# mcu.net
KiCad netlist of a schematic drawn in Altium Designer
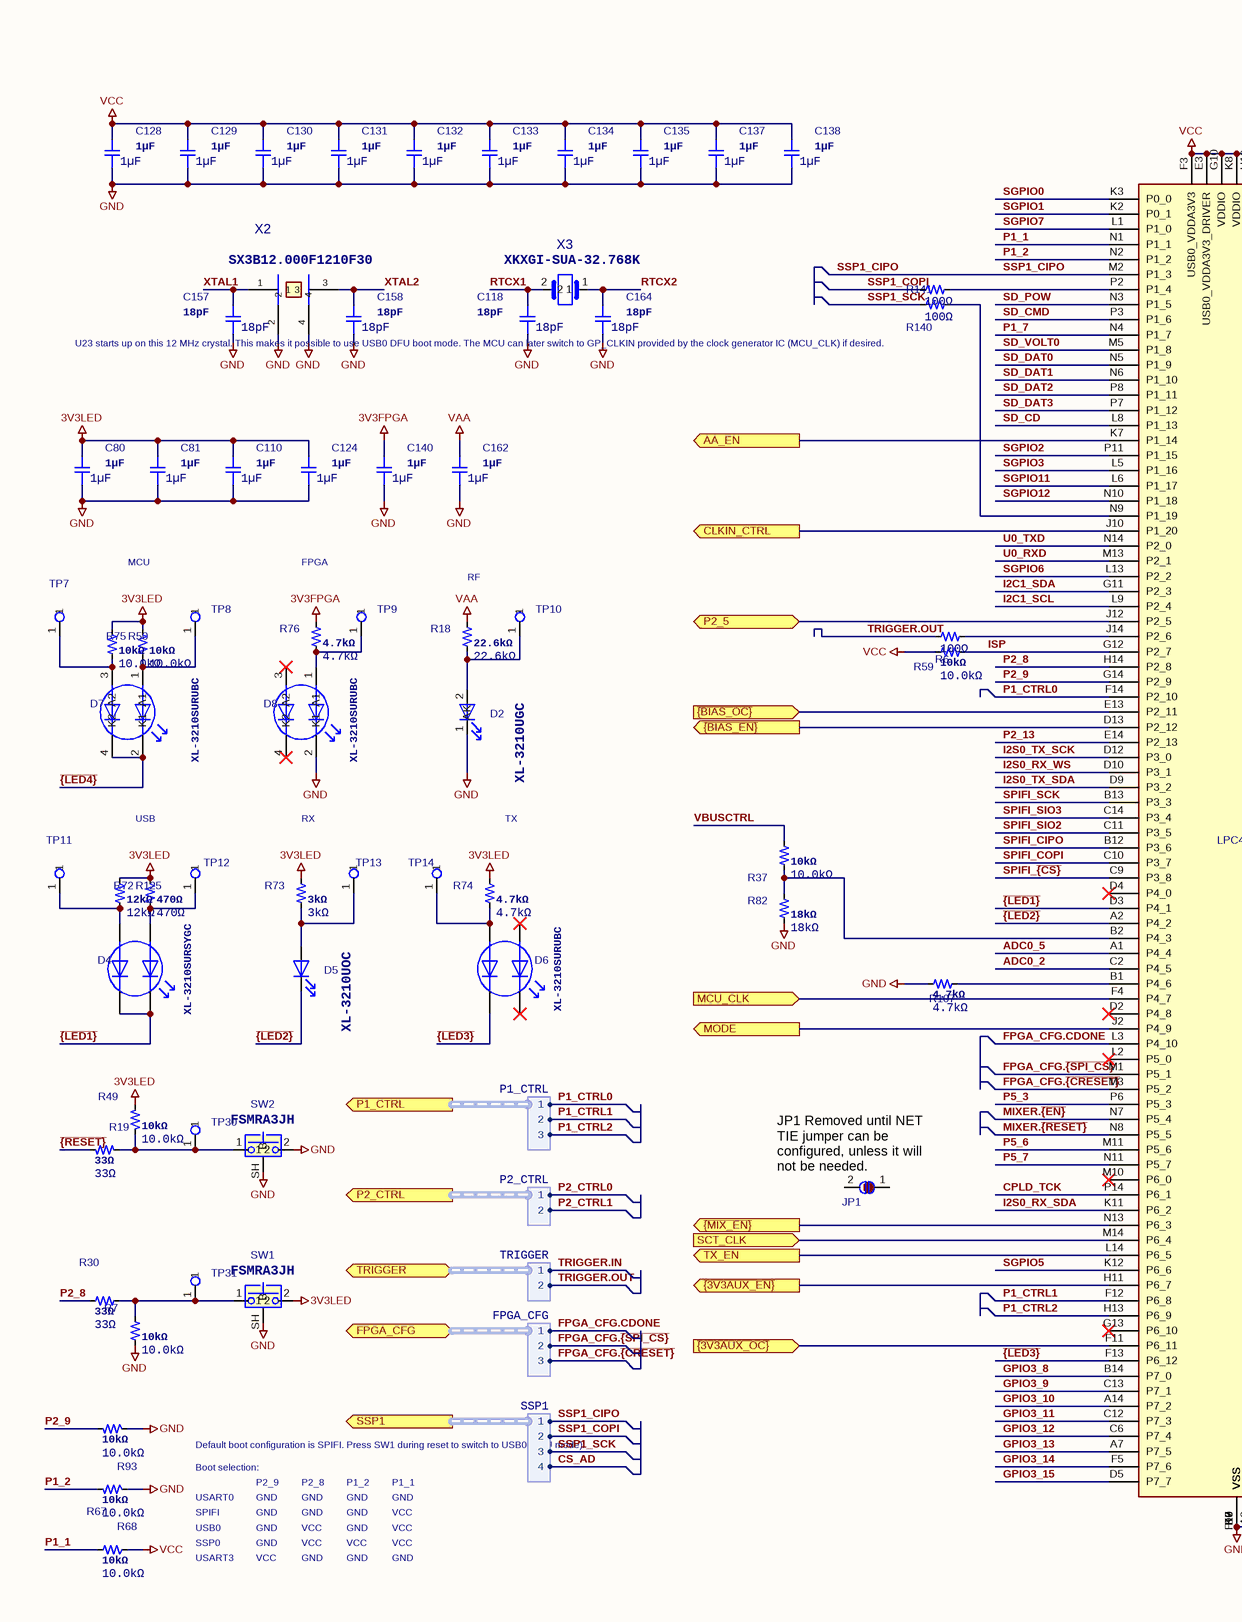
[diagram p0: mcu.SchDoc, left]
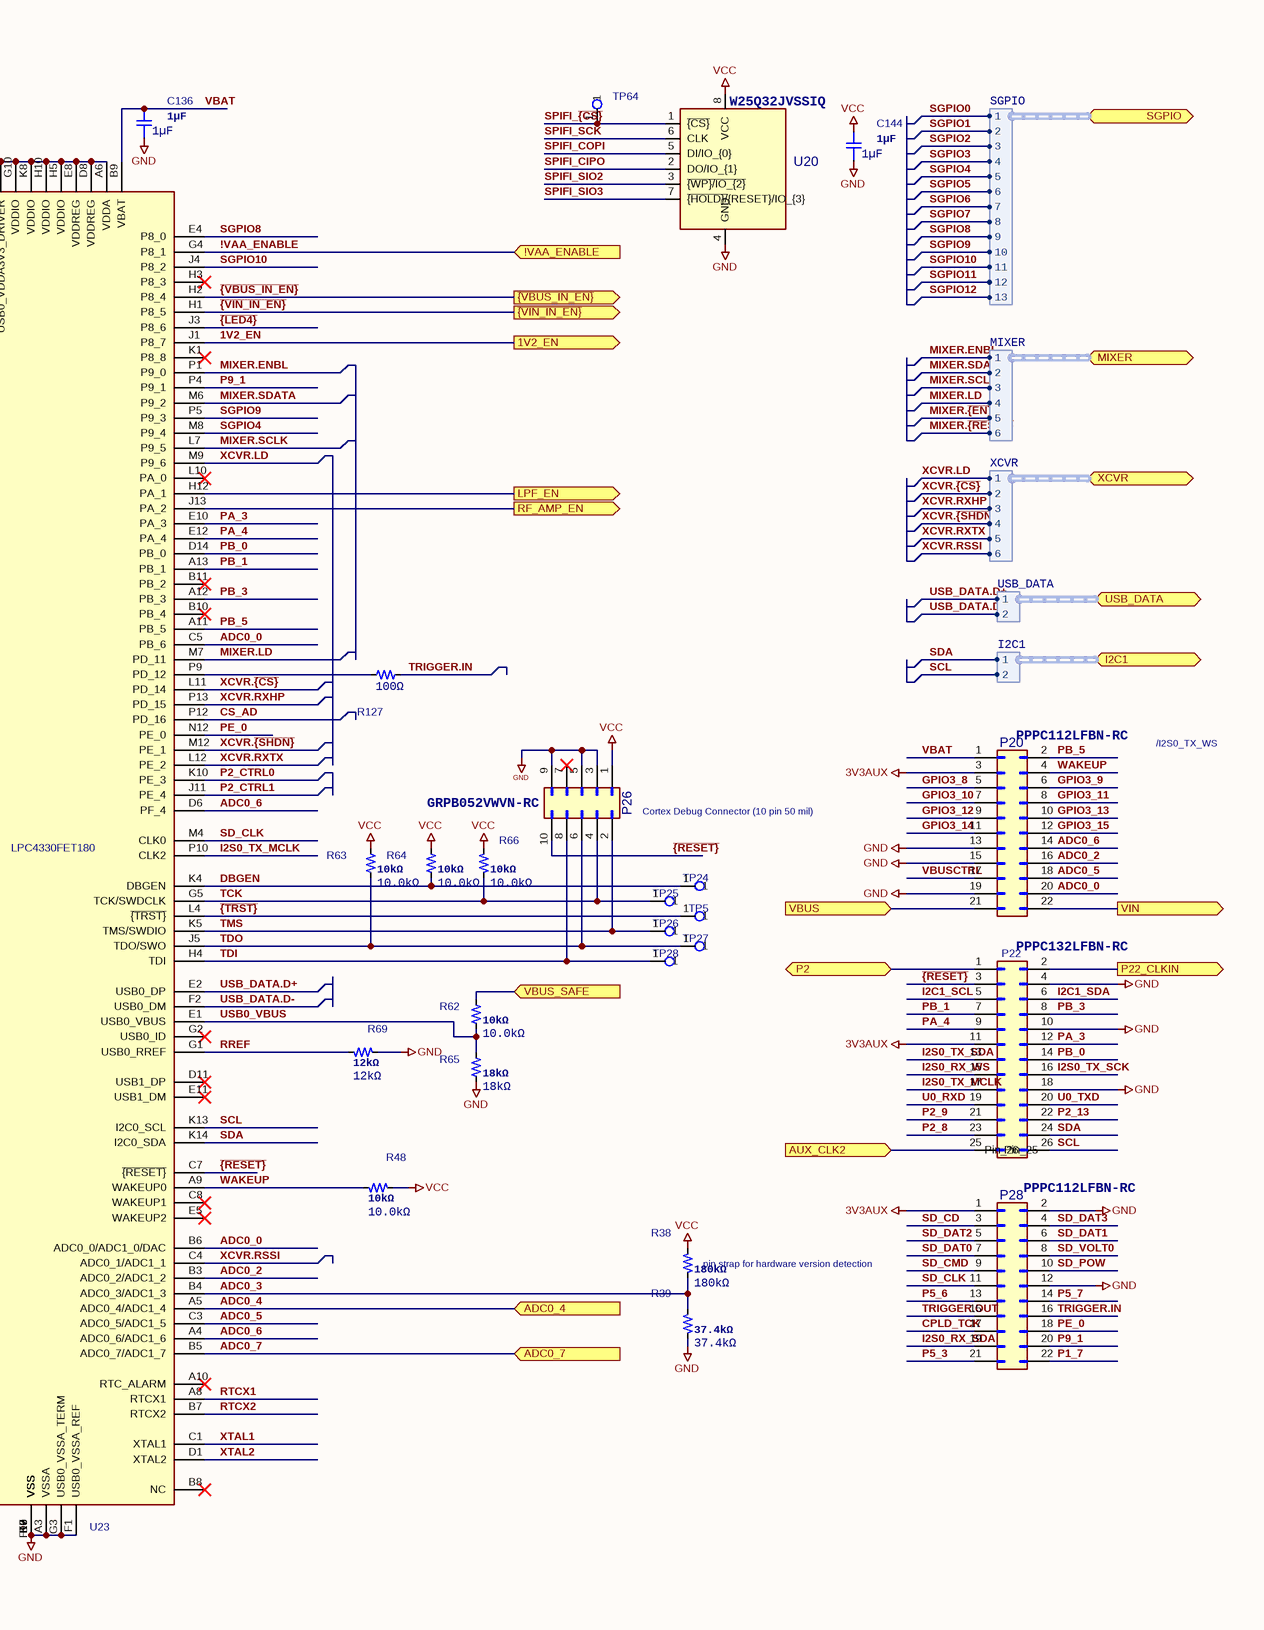
[diagram p1: mcu.SchDoc, right]

(export (version "E")
  (design (tool "Eeschema 10.0.6"))
  (components
    (comp (ref "C80")
      (value "1µF")
      (footprint "CAPC0402(1005)33_L")
      (description "CAP, CERM, 1 µF, 25 V, +/-10%, 0402, X7R")
      (fields
        (field (name "CAPACITANCE") "1µF")
        (field (name "VOLTAGE") "25V")
        (field (name "TOLERANCE") "10%")
      )
      (libsource (lib "Micro Nova LLC") (part "Standard Capacitor"))
    )
    (comp (ref "C81")
      (value "1µF")
      (footprint "CAPC0402(1005)33_L")
      (description "CAP, CERM, 1 µF, 25 V, +/-10%, 0402, X7R")
      (fields
        (field (name "CAPACITANCE") "1µF")
        (field (name "VOLTAGE") "25V")
        (field (name "TOLERANCE") "10%")
      )
      (libsource (lib "Micro Nova LLC") (part "Standard Capacitor"))
    )
    (comp (ref "C110")
      (value "1µF")
      (footprint "CAPC0402(1005)33_L")
      (description "CAP, CERM, 1 µF, 25 V, +/-10%, 0402, X7R")
      (fields
        (field (name "CAPACITANCE") "1µF")
        (field (name "VOLTAGE") "25V")
        (field (name "TOLERANCE") "10%")
      )
      (libsource (lib "Micro Nova LLC") (part "Standard Capacitor"))
    )
    (comp (ref "C118")
      (value "18pF")
      (footprint "CAPC0402(1005)33_L")
      (description "CAP, CERM, 18 pF, 50 V, +/-5%, 0402, C0G")
      (fields
        (field (name "CAPACITANCE") "18pF")
        (field (name "TOLERANCE") "5%")
        (field (name "PARTNUMBER") "CGA2B2NP01H220J050BA")
      )
      (libsource (lib "Micro Nova LLC") (part "Standard Capacitor"))
    )
    (comp (ref "C124")
      (value "1µF")
      (footprint "CAPC0402(1005)33_L")
      (description "CAP, CERM, 1 µF, 25 V, +/-10%, 0402, X7R")
      (fields
        (field (name "CAPACITANCE") "1µF")
        (field (name "VOLTAGE") "25V")
        (field (name "TOLERANCE") "10%")
      )
      (libsource (lib "Micro Nova LLC") (part "Standard Capacitor"))
    )
    (comp (ref "C128")
      (value "1µF")
      (footprint "CAPC0402(1005)33_L")
      (description "CAP, CERM, 1 µF, 25 V, +/-10%, 0402, X7R")
      (fields
        (field (name "CAPACITANCE") "1µF")
        (field (name "VOLTAGE") "25V")
        (field (name "TOLERANCE") "10%")
      )
      (libsource (lib "Micro Nova LLC") (part "Standard Capacitor"))
    )
    (comp (ref "C129")
      (value "1µF")
      (footprint "CAPC0402(1005)33_L")
      (description "CAP, CERM, 1 µF, 25 V, +/-10%, 0402, X7R")
      (fields
        (field (name "CAPACITANCE") "1µF")
        (field (name "VOLTAGE") "25V")
        (field (name "TOLERANCE") "10%")
      )
      (libsource (lib "Micro Nova LLC") (part "Standard Capacitor"))
    )
    (comp (ref "C130")
      (value "1µF")
      (footprint "CAPC0402(1005)33_L")
      (description "CAP, CERM, 1 µF, 25 V, +/-10%, 0402, X7R")
      (fields
        (field (name "CAPACITANCE") "1µF")
        (field (name "VOLTAGE") "25V")
        (field (name "TOLERANCE") "10%")
      )
      (libsource (lib "Micro Nova LLC") (part "Standard Capacitor"))
    )
    (comp (ref "C131")
      (value "1µF")
      (footprint "CAPC0402(1005)33_L")
      (description "CAP, CERM, 1 µF, 25 V, +/-10%, 0402, X7R")
      (fields
        (field (name "CAPACITANCE") "1µF")
        (field (name "VOLTAGE") "25V")
        (field (name "TOLERANCE") "10%")
      )
      (libsource (lib "Micro Nova LLC") (part "Standard Capacitor"))
    )
    (comp (ref "C132")
      (value "1µF")
      (footprint "CAPC0402(1005)33_L")
      (description "CAP, CERM, 1 µF, 25 V, +/-10%, 0402, X7R")
      (fields
        (field (name "CAPACITANCE") "1µF")
        (field (name "VOLTAGE") "25V")
        (field (name "TOLERANCE") "10%")
      )
      (libsource (lib "Micro Nova LLC") (part "Standard Capacitor"))
    )
    (comp (ref "C133")
      (value "1µF")
      (footprint "CAPC0402(1005)33_L")
      (description "CAP, CERM, 1 µF, 25 V, +/-10%, 0402, X7R")
      (fields
        (field (name "CAPACITANCE") "1µF")
        (field (name "VOLTAGE") "25V")
        (field (name "TOLERANCE") "10%")
      )
      (libsource (lib "Micro Nova LLC") (part "Standard Capacitor"))
    )
    (comp (ref "C134")
      (value "1µF")
      (footprint "CAPC0402(1005)33_L")
      (description "CAP, CERM, 1 µF, 25 V, +/-10%, 0402, X7R")
      (fields
        (field (name "CAPACITANCE") "1µF")
        (field (name "VOLTAGE") "25V")
        (field (name "TOLERANCE") "10%")
      )
      (libsource (lib "Micro Nova LLC") (part "Standard Capacitor"))
    )
    (comp (ref "C135")
      (value "1µF")
      (footprint "CAPC0402(1005)33_L")
      (description "CAP, CERM, 1 µF, 25 V, +/-10%, 0402, X7R")
      (fields
        (field (name "CAPACITANCE") "1µF")
        (field (name "VOLTAGE") "25V")
        (field (name "TOLERANCE") "10%")
      )
      (libsource (lib "Micro Nova LLC") (part "Standard Capacitor"))
    )
    (comp (ref "C136")
      (value "1µF")
      (footprint "CAPC0402(1005)33_L")
      (description "CAP, CERM, 1 µF, 25 V, +/-10%, 0402, X7R")
      (fields
        (field (name "CAPACITANCE") "1µF")
        (field (name "VOLTAGE") "25V")
        (field (name "TOLERANCE") "10%")
      )
      (libsource (lib "Micro Nova LLC") (part "Standard Capacitor"))
    )
    (comp (ref "C137")
      (value "1µF")
      (footprint "CAPC0402(1005)33_L")
      (description "CAP, CERM, 1 µF, 25 V, +/-10%, 0402, X7R")
      (fields
        (field (name "CAPACITANCE") "1µF")
        (field (name "VOLTAGE") "25V")
        (field (name "TOLERANCE") "10%")
      )
      (libsource (lib "Micro Nova LLC") (part "Standard Capacitor"))
    )
    (comp (ref "C138")
      (value "1µF")
      (footprint "CAPC0402(1005)33_L")
      (description "CAP, CERM, 1 µF, 25 V, +/-10%, 0402, X7R")
      (fields
        (field (name "CAPACITANCE") "1µF")
        (field (name "VOLTAGE") "25V")
        (field (name "TOLERANCE") "10%")
      )
      (libsource (lib "Micro Nova LLC") (part "Standard Capacitor"))
    )
    (comp (ref "C140")
      (value "1µF")
      (footprint "CAPC0402(1005)33_L")
      (description "CAP, CERM, 1 µF, 25 V, +/-10%, 0402, X7R")
      (fields
        (field (name "CAPACITANCE") "1µF")
        (field (name "VOLTAGE") "25V")
        (field (name "TOLERANCE") "10%")
      )
      (libsource (lib "Micro Nova LLC") (part "Standard Capacitor"))
    )
    (comp (ref "C144")
      (value "1µF")
      (footprint "CAPC0402(1005)33_L")
      (description "CAP, CERM, 1 µF, 25 V, +/-10%, 0402, X7R")
      (fields
        (field (name "CAPACITANCE") "1µF")
        (field (name "VOLTAGE") "25V")
        (field (name "TOLERANCE") "10%")
      )
      (libsource (lib "Micro Nova LLC") (part "Standard Capacitor"))
    )
    (comp (ref "C157")
      (value "18pF")
      (footprint "CAPC0402(1005)33_L")
      (description "CAP, CERM, 18 pF, 50 V, +/-5%, 0402, C0G")
      (fields
        (field (name "CAPACITANCE") "18pF")
        (field (name "TOLERANCE") "5%")
        (field (name "PARTNUMBER") "CGA2B2NP01H220J050BA")
      )
      (libsource (lib "Micro Nova LLC") (part "Standard Capacitor"))
    )
    (comp (ref "C158")
      (value "18pF")
      (footprint "CAPC0402(1005)33_L")
      (description "CAP, CERM, 18 pF, 50 V, +/-5%, 0402, C0G")
      (fields
        (field (name "CAPACITANCE") "18pF")
        (field (name "TOLERANCE") "5%")
        (field (name "PARTNUMBER") "CGA2B2NP01H220J050BA")
      )
      (libsource (lib "Micro Nova LLC") (part "Standard Capacitor"))
    )
    (comp (ref "C162")
      (value "1µF")
      (footprint "CAPC0402(1005)33_L")
      (description "CAP, CERM, 1 µF, 25 V, +/-10%, 0402, X7R")
      (fields
        (field (name "CAPACITANCE") "1µF")
        (field (name "VOLTAGE") "25V")
        (field (name "TOLERANCE") "10%")
      )
      (libsource (lib "Micro Nova LLC") (part "Standard Capacitor"))
    )
    (comp (ref "C164")
      (value "18pF")
      (footprint "CAPC0402(1005)33_L")
      (description "CAP, CERM, 18 pF, 50 V, +/-5%, 0402, C0G")
      (fields
        (field (name "CAPACITANCE") "18pF")
        (field (name "TOLERANCE") "5%")
        (field (name "PARTNUMBER") "CGA2B2NP01H220J050BA")
      )
      (libsource (lib "Micro Nova LLC") (part "Standard Capacitor"))
    )
    (comp (ref "D2")
      (value "LED")
      (footprint "LED_Single_Xinglight_XL-3210_Horizontal")
      (fields (field (name "MANUFACTURER") "Xinglight") (field (name "PART NUMBER") "XL-3210UGC"))
      (libsource (lib "Device") (part "LED"))
    )
    (comp (ref "D4")
      (value "LED")
      (footprint "LED_Dual_Xinglight_XL-3210_Horizontal")
      (fields (field (name "MANUFACTURER") "Xinglight") (field (name "PART NUMBER") "XL-3210SURSYGC"))
      (libsource (lib "Device") (part "LED_Dual_AKAK"))
    )
    (comp (ref "D5")
      (value "LED")
      (footprint "LED_Single_Xinglight_XL-3210_Horizontal")
      (fields (field (name "MANUFACTURER") "Xinglight") (field (name "PART NUMBER") "XL-3210UOC"))
      (libsource (lib "") (part "LED_1"))
    )
    (comp (ref "D6")
      (value "LED")
      (footprint "LED_Dual_Xinglight_XL-3210_Horizontal")
      (fields (field (name "MANUFACTURER") "Xinglight") (field (name "PART NUMBER") "XL-3210SURUBC"))
      (libsource (lib "Device") (part "LED_Dual_AKAK"))
    )
    (comp (ref "D7")
      (value "LED")
      (footprint "LED_Dual_Xinglight_XL-3210_Horizontal")
      (fields (field (name "MANUFACTURER") "Xinglight") (field (name "PART NUMBER") "XL-3210SURUBC"))
      (libsource (lib "") (part "LED_Dual_AKAK_1"))
    )
    (comp (ref "D8")
      (value "LED")
      (footprint "LED_Dual_Xinglight_XL-3210_Horizontal")
      (fields (field (name "MANUFACTURER") "Xinglight") (field (name "PART NUMBER") "XL-3210SURUBC"))
      (libsource (lib "") (part "LED_Dual_AKAK_1"))
    )
    (comp (ref "JP1")
      (value "SolderJumper_2_Bridged")
      (footprint "SolderJumper-2_P1.3mm_Bridged_RoundedPad1.0x1.5mm")
      (libsource (lib "Jumper") (part "SolderJumper_2_Bridged"))
    )
    (comp (ref "P20")
      (value "HEADER_2x11")
      (footprint "PinSocket_2x11_P2.54mm_Vertical_Flipped")
      (fields (field (name "MANUFACTURER") "Sullins") (field (name "PART NUMBER") "PPPC112LFBN-RC"))
      (libsource (lib "Connector_Generic") (part "Conn_02x11_Odd_Even"))
    )
    (comp (ref "P22")
      (value "HEADER_2x13")
      (footprint "PinSocket_2x13_P2.54mm_Vertical_Flipped")
      (fields (field (name "MANUFACTURER") "Sullins") (field (name "PART NUMBER") "PPPC132LFBN-RC"))
      (libsource (lib "Connector_Generic") (part "Conn_02x13_Odd_Even"))
    )
    (comp (ref "P26")
      (value "LPC_JTAG")
      (footprint "PinHeader_2x05_P1.27mm_Vertical")
      (fields (field (name "MANUFACTURER") "Sullins") (field (name "PART NUMBER") "GRPB052VWVN-RC"))
      (libsource (lib "Connector_Generic") (part "Conn_02x05_Odd_Even"))
    )
    (comp (ref "P28")
      (value "HEADER_2x11")
      (footprint "PinSocket_2x11_P2.54mm_Vertical_Flipped")
      (fields (field (name "MANUFACTURER") "Sullins") (field (name "PART NUMBER") "PPPC112LFBN-RC"))
      (libsource (lib "Connector_Generic") (part "Conn_02x11_Odd_Even"))
    )
    (comp (ref "R6")
      (value "MN-RES-0201-100Ω-1/20W")
      (footprint "RESC0201(0603)_N")
      (description "Resistor, 100Ω, 1%, 1/20W (50mW), 0201")
      (fields
        (field (name "RESISTANCE") "100Ω")
        (field (name "TOLERANCE") "5%")
        (field (name "PARTNUMBER") "RC0201JR-13100RL")
      )
      (libsource (lib "Micro Nova LLC") (part "Standard Resistor"))
    )
    (comp (ref "R7")
      (value "10kΩ")
      (footprint "RESC0402(1005)")
      (description "Resistor, 10.0KΩ, 1%, 1/5W (200mW), 0402")
      (fields
        (field (name "RESISTANCE") "10.0kΩ")
        (field (name "TOLERANCE") "1%")
        (field (name "PARTNUMBER") "CRCW040210K0FKEDHP")
      )
      (libsource (lib "Micro Nova LLC") (part "Standard Resistor"))
    )
    (comp (ref "R18")
      (value "22.6kΩ")
      (footprint "RESC0201(0603)_N")
      (description "Resistor, 22.6KΩ, 1%, 1/20W (50mW), 0201")
      (fields
        (field (name "RESISTANCE") "22.6kΩ")
        (field (name "PARTNUMBER") "RC0201JR-13100RL")
        (field (name "TOLERANCE") "1%")
      )
      (libsource (lib "Micro Nova LLC") (part "Standard Resistor"))
    )
    (comp (ref "R19")
      (value "33Ω")
      (footprint "RESC0201(0603)_N")
      (description "Resistor, 33Ω, 1%, 1/20W (50mW), 0201")
      (fields
        (field (name "RESISTANCE") "33Ω")
        (field (name "TOLERANCE") "5%")
        (field (name "PARTNUMBER") "RC0201JR-13100RL")
      )
      (libsource (lib "Micro Nova LLC") (part "Standard Resistor"))
    )
    (comp (ref "R30")
      (value "33Ω")
      (footprint "RESC0201(0603)_N")
      (description "Resistor, 33Ω, 1%, 1/20W (50mW), 0201")
      (fields
        (field (name "RESISTANCE") "33Ω")
        (field (name "TOLERANCE") "5%")
        (field (name "PARTNUMBER") "RC0201JR-13100RL")
      )
      (libsource (lib "Micro Nova LLC") (part "Standard Resistor"))
    )
    (comp (ref "R37")
      (value "10kΩ")
      (footprint "RESC0402(1005)")
      (description "Resistor, 10.0KΩ, 1%, 1/5W (200mW), 0402")
      (fields
        (field (name "RESISTANCE") "10.0kΩ")
        (field (name "TOLERANCE") "1%")
        (field (name "PARTNUMBER") "CRCW040210K0FKEDHP")
      )
      (libsource (lib "Micro Nova LLC") (part "Standard Resistor"))
    )
    (comp (ref "R38")
      (value "180kΩ")
      (footprint "RESC0402(1005)")
      (description "Resistor, 180KΩ, 1%, 1/16W (66mW), 0402")
      (fields
        (field (name "TOLERANCE") "1%")
        (field (name "RESISTANCE") "180kΩ")
        (field (name "PARTNUMBER") "RC0402FR-07180KL")
      )
      (libsource (lib "Micro Nova LLC") (part "Standard Resistor"))
    )
    (comp (ref "R39")
      (value "37.4kΩ")
      (footprint "RESC0402(1005)")
      (description "Resistor, 37.4KΩ, 1%, 1/16W (66mW), 0402")
      (fields
        (field (name "TOLERANCE") "1%")
        (field (name "RESISTANCE") "37.4kΩ")
        (field (name "PARTNUMBER") "RC0402FR-0737K4L")
      )
      (libsource (lib "Micro Nova LLC") (part "Standard Resistor"))
    )
    (comp (ref "R48")
      (value "10kΩ")
      (footprint "RESC0402(1005)")
      (description "Resistor, 10.0KΩ, 1%, 1/5W (200mW), 0402")
      (fields
        (field (name "RESISTANCE") "10.0kΩ")
        (field (name "TOLERANCE") "1%")
        (field (name "PARTNUMBER") "CRCW040210K0FKEDHP")
      )
      (libsource (lib "Micro Nova LLC") (part "Standard Resistor"))
    )
    (comp (ref "R49")
      (value "10kΩ")
      (footprint "RESC0402(1005)")
      (description "Resistor, 10.0KΩ, 1%, 1/5W (200mW), 0402")
      (fields
        (field (name "RESISTANCE") "10.0kΩ")
        (field (name "TOLERANCE") "1%")
        (field (name "PARTNUMBER") "CRCW040210K0FKEDHP")
      )
      (libsource (lib "Micro Nova LLC") (part "Standard Resistor"))
    )
    (comp (ref "R50")
      (value "10kΩ")
      (footprint "RESC0402(1005)")
      (description "Resistor, 10.0KΩ, 1%, 1/5W (200mW), 0402")
      (fields
        (field (name "RESISTANCE") "10.0kΩ")
        (field (name "TOLERANCE") "1%")
        (field (name "PARTNUMBER") "CRCW040210K0FKEDHP")
      )
      (libsource (lib "Micro Nova LLC") (part "Standard Resistor"))
    )
    (comp (ref "R59")
      (value "10kΩ")
      (footprint "RESC0402(1005)")
      (description "Resistor, 10.0KΩ, 1%, 1/5W (200mW), 0402")
      (fields
        (field (name "RESISTANCE") "10.0kΩ")
        (field (name "TOLERANCE") "1%")
        (field (name "PARTNUMBER") "CRCW040210K0FKEDHP")
      )
      (libsource (lib "Micro Nova LLC") (part "Standard Resistor"))
    )
    (comp (ref "R62")
      (value "10kΩ")
      (footprint "RESC0402(1005)")
      (description "Resistor, 10.0KΩ, 1%, 1/5W (200mW), 0402")
      (fields
        (field (name "RESISTANCE") "10.0kΩ")
        (field (name "TOLERANCE") "1%")
        (field (name "PARTNUMBER") "CRCW040210K0FKEDHP")
      )
      (libsource (lib "Micro Nova LLC") (part "Standard Resistor"))
    )
    (comp (ref "R63")
      (value "10kΩ")
      (footprint "RESC0402(1005)")
      (description "Resistor, 10.0KΩ, 1%, 1/5W (200mW), 0402")
      (fields
        (field (name "RESISTANCE") "10.0kΩ")
        (field (name "TOLERANCE") "1%")
        (field (name "PARTNUMBER") "CRCW040210K0FKEDHP")
      )
      (libsource (lib "Micro Nova LLC") (part "Standard Resistor"))
    )
    (comp (ref "R64")
      (value "10kΩ")
      (footprint "RESC0402(1005)")
      (description "Resistor, 10.0KΩ, 1%, 1/5W (200mW), 0402")
      (fields
        (field (name "RESISTANCE") "10.0kΩ")
        (field (name "TOLERANCE") "1%")
        (field (name "PARTNUMBER") "CRCW040210K0FKEDHP")
      )
      (libsource (lib "Micro Nova LLC") (part "Standard Resistor"))
    )
    (comp (ref "R65")
      (value "18kΩ")
      (footprint "RESC0402(1005)")
      (description "Resistor, 18KΩ, 5%, 1/16W (66mW), 0402")
      (fields
        (field (name "RESISTANCE") "18kΩ")
        (field (name "PARTNUMBER") "RC0402JR-0718KL")
        (field (name "TOLERANCE") "5%")
      )
      (libsource (lib "Micro Nova LLC") (part "Standard Resistor"))
    )
    (comp (ref "R66")
      (value "10kΩ")
      (footprint "RESC0402(1005)")
      (description "Resistor, 10.0KΩ, 1%, 1/5W (200mW), 0402")
      (fields
        (field (name "RESISTANCE") "10.0kΩ")
        (field (name "TOLERANCE") "1%")
        (field (name "PARTNUMBER") "CRCW040210K0FKEDHP")
      )
      (libsource (lib "Micro Nova LLC") (part "Standard Resistor"))
    )
    (comp (ref "R67")
      (value "10kΩ")
      (footprint "RESC0402(1005)")
      (description "Resistor, 10.0KΩ, 1%, 1/5W (200mW), 0402")
      (fields
        (field (name "RESISTANCE") "10.0kΩ")
        (field (name "TOLERANCE") "1%")
        (field (name "PARTNUMBER") "CRCW040210K0FKEDHP")
      )
      (libsource (lib "Micro Nova LLC") (part "Standard Resistor"))
    )
    (comp (ref "R68")
      (value "10kΩ")
      (footprint "RESC0402(1005)")
      (description "Resistor, 10.0KΩ, 1%, 1/5W (200mW), 0402")
      (fields
        (field (name "RESISTANCE") "10.0kΩ")
        (field (name "TOLERANCE") "1%")
        (field (name "PARTNUMBER") "CRCW040210K0FKEDHP")
      )
      (libsource (lib "Micro Nova LLC") (part "Standard Resistor"))
    )
    (comp (ref "R69")
      (value "12kΩ")
      (footprint "RESC0201(0603)_N")
      (description "Resistor, 12KΩ, 1%, 1/20W (50mW), 0201")
      (fields
        (field (name "TOLERANCE") "1%")
        (field (name "RESISTANCE") "12kΩ")
        (field (name "PARTNUMBER") "RC0201FR-0712KL")
      )
      (libsource (lib "Micro Nova LLC") (part "Standard Resistor"))
    )
    (comp (ref "R72")
      (value "470Ω")
      (footprint "RESC0201(0603)_N")
      (description "Resistor, 470Ω, 1%, 1/20W (50mW), 0201")
      (fields
        (field (name "RESISTANCE") "470Ω")
        (field (name "TOLERANCE") "5%")
        (field (name "PARTNUMBER") "RC0201JR-07470RL")
      )
      (libsource (lib "Micro Nova LLC") (part "Standard Resistor"))
    )
    (comp (ref "R73")
      (value "3kΩ")
      (footprint "RESC0402(1005)")
      (description "Resistor, 3KΩ, 1%, 1/16W (66mW), 0402")
      (fields
        (field (name "RESISTANCE") "3kΩ")
        (field (name "PARTNUMBER") "CRCW04023R32FKED")
        (field (name "TOLERANCE") "5%")
      )
      (libsource (lib "Micro Nova LLC") (part "Standard Resistor"))
    )
    (comp (ref "R74")
      (value "4.7kΩ")
      (footprint "RESC0201(0603)_N")
      (description "Resistor, 4.7KΩ, 1%, 1/20W (50mW), 0201")
      (fields
        (field (name "RESISTANCE") "4.7kΩ")
        (field (name "TOLERANCE") "1%")
        (field (name "PARTNUMBER") "RC0201JR-13100RL")
      )
      (libsource (lib "Micro Nova LLC") (part "Standard Resistor"))
    )
    (comp (ref "R75")
      (value "10kΩ")
      (footprint "RESC0402(1005)")
      (description "Resistor, 10.0KΩ, 1%, 1/5W (200mW), 0402")
      (fields
        (field (name "RESISTANCE") "10.0kΩ")
        (field (name "TOLERANCE") "1%")
        (field (name "PARTNUMBER") "CRCW040210K0FKEDHP")
      )
      (libsource (lib "Micro Nova LLC") (part "Standard Resistor"))
    )
    (comp (ref "R76")
      (value "4.7kΩ")
      (footprint "RESC0201(0603)_N")
      (description "Resistor, 4.7KΩ, 1%, 1/20W (50mW), 0201")
      (fields
        (field (name "RESISTANCE") "4.7kΩ")
        (field (name "TOLERANCE") "1%")
        (field (name "PARTNUMBER") "RC0201JR-13100RL")
      )
      (libsource (lib "Micro Nova LLC") (part "Standard Resistor"))
    )
    (comp (ref "R82")
      (value "18kΩ")
      (footprint "RESC0402(1005)")
      (description "Resistor, 18KΩ, 5%, 1/16W (66mW), 0402")
      (fields
        (field (name "RESISTANCE") "18kΩ")
        (field (name "PARTNUMBER") "RC0402JR-0718KL")
        (field (name "TOLERANCE") "5%")
      )
      (libsource (lib "Micro Nova LLC") (part "Standard Resistor"))
    )
    (comp (ref "R93")
      (value "10kΩ")
      (footprint "RESC0402(1005)")
      (description "Resistor, 10.0KΩ, 1%, 1/5W (200mW), 0402")
      (fields
        (field (name "RESISTANCE") "10.0kΩ")
        (field (name "TOLERANCE") "1%")
        (field (name "PARTNUMBER") "CRCW040210K0FKEDHP")
      )
      (libsource (lib "Micro Nova LLC") (part "Standard Resistor"))
    )
    (comp (ref "R107")
      (value "4.7kΩ")
      (footprint "RESC0201(0603)_N")
      (description "Resistor, 4.7KΩ, 1%, 1/20W (50mW), 0201")
      (fields
        (field (name "RESISTANCE") "4.7kΩ")
        (field (name "TOLERANCE") "1%")
        (field (name "PARTNUMBER") "RC0201JR-13100RL")
      )
      (libsource (lib "Micro Nova LLC") (part "Standard Resistor"))
    )
    (comp (ref "R125")
      (value "12kΩ")
      (footprint "RESC0201(0603)_N")
      (description "Resistor, 12KΩ, 1%, 1/20W (50mW), 0201")
      (fields
        (field (name "RESISTANCE") "12kΩ")
        (field (name "TOLERANCE") "1%")
        (field (name "PARTNUMBER") "RC0201FR-0712KL")
      )
      (libsource (lib "Micro Nova LLC") (part "Standard Resistor"))
    )
    (comp (ref "R127")
      (value "MN-RES-0201-100Ω-1/20W")
      (footprint "RESC0201(0603)_N")
      (description "Resistor, 100Ω, 1%, 1/20W (50mW), 0201")
      (fields
        (field (name "RESISTANCE") "100Ω")
        (field (name "TOLERANCE") "5%")
        (field (name "PARTNUMBER") "RC0201JR-13100RL")
      )
      (libsource (lib "Micro Nova LLC") (part "Standard Resistor"))
    )
    (comp (ref "R140")
      (value "MN-RES-0201-100Ω-1/20W")
      (footprint "RESC0201(0603)_N")
      (description "Resistor, 100Ω, 1%, 1/20W (50mW), 0201")
      (fields
        (field (name "RESISTANCE") "100Ω")
        (field (name "TOLERANCE") "5%")
        (field (name "PARTNUMBER") "RC0201JR-13100RL")
      )
      (libsource (lib "Micro Nova LLC") (part "Standard Resistor"))
    )
    (comp (ref "R141")
      (value "MN-RES-0201-100Ω-1/20W")
      (footprint "RESC0201(0603)_N")
      (description "Resistor, 100Ω, 1%, 1/20W (50mW), 0201")
      (fields
        (field (name "RESISTANCE") "100Ω")
        (field (name "TOLERANCE") "5%")
        (field (name "PARTNUMBER") "RC0201JR-13100RL")
      )
      (libsource (lib "Micro Nova LLC") (part "Standard Resistor"))
    )
    (comp (ref "SW1")
      (value "SWITCH")
      (footprint "SW_Tactile_SPST_Angled_PTS645Vx58-2LFS")
      (fields (field (name "MANUFACTURER") "TE Connectivity") (field (name "PART NUMBER") "FSMRA3JH"))
      (libsource (lib "Switch") (part "SW_Push_Shielded"))
    )
    (comp (ref "SW2")
      (value "SWITCH")
      (footprint "SW_Tactile_SPST_Angled_PTS645Vx58-2LFS")
      (fields (field (name "MANUFACTURER") "TE Connectivity") (field (name "PART NUMBER") "FSMRA3JH"))
      (libsource (lib "Switch") (part "SW_Push_Shielded"))
    )
    (comp (ref "TP5")
      (value "TestPoint")
      (footprint "TestPoint_Pad_D1.0mm")
      (libsource (lib "Connector") (part "TestPoint"))
    )
    (comp (ref "TP7")
      (value "TestPoint")
      (footprint "TestPoint_Pad_D1.0mm")
      (libsource (lib "Connector") (part "TestPoint"))
    )
    (comp (ref "TP8")
      (value "TestPoint")
      (footprint "TestPoint_Pad_D1.0mm")
      (libsource (lib "Connector") (part "TestPoint"))
    )
    (comp (ref "TP9")
      (value "TestPoint")
      (footprint "TestPoint_Pad_D1.0mm")
      (libsource (lib "Connector") (part "TestPoint"))
    )
    (comp (ref "TP10")
      (value "TestPoint")
      (footprint "TestPoint_Pad_D1.0mm")
      (libsource (lib "Connector") (part "TestPoint"))
    )
    (comp (ref "TP11")
      (value "TestPoint")
      (footprint "TestPoint_Pad_D1.0mm")
      (libsource (lib "Connector") (part "TestPoint"))
    )
    (comp (ref "TP12")
      (value "TestPoint")
      (footprint "TestPoint_Pad_D1.0mm")
      (libsource (lib "Connector") (part "TestPoint"))
    )
    (comp (ref "TP13")
      (value "TestPoint")
      (footprint "TestPoint_Pad_D1.0mm")
      (libsource (lib "Connector") (part "TestPoint"))
    )
    (comp (ref "TP14")
      (value "TestPoint")
      (footprint "TestPoint_Pad_D1.0mm")
      (libsource (lib "Connector") (part "TestPoint"))
    )
    (comp (ref "TP24")
      (value "TestPoint")
      (footprint "TestPoint_Pad_D1.0mm")
      (libsource (lib "Connector") (part "TestPoint"))
    )
    (comp (ref "TP25")
      (value "TestPoint")
      (footprint "TestPoint_Pad_D1.0mm")
      (libsource (lib "Connector") (part "TestPoint"))
    )
    (comp (ref "TP26")
      (value "TestPoint")
      (footprint "TestPoint_Pad_D1.0mm")
      (libsource (lib "Connector") (part "TestPoint"))
    )
    (comp (ref "TP27")
      (value "TestPoint")
      (footprint "TestPoint_Pad_D1.0mm")
      (libsource (lib "Connector") (part "TestPoint"))
    )
    (comp (ref "TP28")
      (value "TestPoint")
      (footprint "TestPoint_Pad_D1.0mm")
      (libsource (lib "Connector") (part "TestPoint"))
    )
    (comp (ref "TP30")
      (value "TestPoint")
      (footprint "TestPoint_Pad_D1.0mm")
      (libsource (lib "Connector") (part "TestPoint"))
    )
    (comp (ref "TP31")
      (value "TestPoint")
      (footprint "TestPoint_Pad_D1.0mm")
      (libsource (lib "Connector") (part "TestPoint"))
    )
    (comp (ref "TP64")
      (value "TestPoint")
      (footprint "TestPoint_Pad_D1.0mm")
      (libsource (lib "Connector") (part "TestPoint"))
    )
    (comp (ref "U20")
      (value "W25Q32")
      (footprint "SOIC-8_5.3x5.3mm_P1.27mm")
      (fields (field (name "MANUFACTURER") "Winbond") (field (name "PART NUMBER") "W25Q32JVSSIQ"))
      (libsource (lib "Memory_Flash") (part "W25Q32JVSS"))
    )
    (comp (ref "U23")
      (value "LPC4330FET180")
      (footprint "TFBGA-180_12x12mm_Layout14x14_P0.8mm")
      (fields (field (name "MANUFACTURER") "NXP") (field (name "PART NUMBER") "LPC4330FET180"))
      (libsource (lib "praline") (part "LPC43xxFET180"))
    )
    (comp (ref "X2")
      (value "MCU_XTAL")
      (footprint "Crystal_SMD_3225-4Pin_3.2x2.5mm")
      (fields
        (field (name "MANUFACTURER") "Shenzhen SCTF Electronics")
        (field (name "PART NUMBER") "SX3B12.000F1210F30")
      )
      (libsource (lib "hackrf") (part "GSG-XTAL4PIN"))
    )
    (comp (ref "X3")
      (value "RTC_XTAL")
      (footprint "Crystal_SMD_3215-2Pin_3.2x1.5mm")
      (fields (field (name "MANUFACTURER") "YXC") (field (name "PART NUMBER") "XKXGI-SUA-32.768K"))
      (libsource (lib "Device") (part "Crystal"))
    )
  )
  (nets
    (net (code "11") (name "/!VAA_ENABLE") (class "Default")
      (node (ref "U23") (pin "G4") (pinfunction "P8_1_G4") (pintype "passive"))
    )
    (net (code "12") (name "/1V2_EN") (class "Default")
      (node (ref "U23") (pin "J1") (pinfunction "P8_7_J1") (pintype "passive"))
    )
    (net (code "13") (name "/AA_EN") (class "Default")
      (node (ref "U23") (pin "K7") (pinfunction "P1_14_K7") (pintype "passive"))
    )
    (net (code "14") (name "/ADC0_0") (class "Default")
      (node (ref "P20") (pin "20") (pinfunction "Pin_20_20") (pintype "passive"))
      (node (ref "U23") (pin "B6") (pinfunction "ADC0_0/ADC1_0/DAC_B6") (pintype "passive"))
      (node (ref "U23") (pin "C5") (pinfunction "PB_6_C5") (pintype "passive"))
    )
    (net (code "15") (name "/ADC0_2") (class "Default")
      (node (ref "P20") (pin "16") (pinfunction "Pin_16_16") (pintype "passive"))
      (node (ref "U23") (pin "B3") (pinfunction "ADC0_2/ADC1_2_B3") (pintype "passive"))
      (node (ref "U23") (pin "C2") (pinfunction "P4_5_C2") (pintype "passive"))
    )
    (net (code "16") (name "/ADC0_3") (class "Default")
      (node (ref "R38") (pin "2") (pinfunction "2_2") (pintype "passive"))
      (node (ref "R39") (pin "1") (pinfunction "1_1") (pintype "passive"))
      (node (ref "U23") (pin "B4") (pinfunction "ADC0_3/ADC1_3_B4") (pintype "passive"))
    )
    (net (code "17") (name "/ADC0_4") (class "Default")
      (node (ref "U23") (pin "A5") (pinfunction "ADC0_4/ADC1_4_A5") (pintype "passive"))
    )
    (net (code "18") (name "/ADC0_5") (class "Default")
      (node (ref "P20") (pin "18") (pinfunction "Pin_18_18") (pintype "passive"))
      (node (ref "U23") (pin "A1") (pinfunction "P4_4_A1") (pintype "passive"))
      (node (ref "U23") (pin "C3") (pinfunction "ADC0_5/ADC1_5_C3") (pintype "passive"))
    )
    (net (code "19") (name "/ADC0_6") (class "Default")
      (node (ref "P20") (pin "14") (pinfunction "Pin_14_14") (pintype "passive"))
      (node (ref "U23") (pin "A4") (pinfunction "ADC0_6/ADC1_6_A4") (pintype "passive"))
      (node (ref "U23") (pin "D6") (pinfunction "PF_4_D6") (pintype "passive"))
    )
    (net (code "20") (name "/ADC0_7") (class "Default")
      (node (ref "U23") (pin "B5") (pinfunction "ADC0_7/ADC1_7_B5") (pintype "passive"))
    )
    (net (code "21") (name "/AUX_CLK2") (class "Default")
      (node (ref "P22") (pin "25") (pinfunction "Pin_25_25") (pintype "passive"))
    )
    (net (code "22") (name "/CLKIN_CTRL") (class "Default")
      (node (ref "U23") (pin "J10") (pinfunction "P1_20_J10") (pintype "passive"))
    )
    (net (code "23") (name "/CPLD_TCK") (class "Default")
      (node (ref "P28") (pin "17") (pinfunction "Pin_17_17") (pintype "passive"))
      (node (ref "U23") (pin "P14") (pinfunction "P6_1_P14") (pintype "passive"))
    )
    (net (code "24") (name "/CS_AD") (class "Default")
      (node (ref "U23") (pin "P12") (pinfunction "PD_16_P12") (pintype "passive"))
    )
    (net (code "25") (name "/DBGEN") (class "Default")
      (node (ref "R64") (pin "2") (pinfunction "2_2") (pintype "passive"))
      (node (ref "TP24") (pin "1") (pinfunction "1_1") (pintype "passive"))
      (node (ref "U23") (pin "K4") (pinfunction "DBGEN_K4") (pintype "passive"))
    )
    (net (code "26") (name "/FPGA_CFG.CDONE") (class "Default")
      (node (ref "U23") (pin "L3") (pinfunction "P4_10_L3") (pintype "passive"))
    )
    (net (code "27") (name "/FPGA_CFG.~{{CRESET}}") (class "Default")
      (node (ref "U23") (pin "M3") (pinfunction "P5_2_M3") (pintype "passive"))
    )
    (net (code "28") (name "/FPGA_CFG.~{{SPI_CS}}") (class "Default")
      (node (ref "U23") (pin "M1") (pinfunction "P5_1_M1") (pintype "passive"))
    )
    (net (code "29") (name "/GPIO3_8") (class "Default")
      (node (ref "P20") (pin "5") (pinfunction "Pin_5_5") (pintype "passive"))
      (node (ref "U23") (pin "B14") (pinfunction "P7_0_B14") (pintype "passive"))
    )
    (net (code "30") (name "/GPIO3_9") (class "Default")
      (node (ref "P20") (pin "6") (pinfunction "Pin_6_6") (pintype "passive"))
      (node (ref "U23") (pin "C13") (pinfunction "P7_1_C13") (pintype "passive"))
    )
    (net (code "31") (name "/GPIO3_10") (class "Default")
      (node (ref "P20") (pin "7") (pinfunction "Pin_7_7") (pintype "passive"))
      (node (ref "U23") (pin "A14") (pinfunction "P7_2_A14") (pintype "passive"))
    )
    (net (code "32") (name "/GPIO3_11") (class "Default")
      (node (ref "P20") (pin "8") (pinfunction "Pin_8_8") (pintype "passive"))
      (node (ref "U23") (pin "C12") (pinfunction "P7_3_C12") (pintype "passive"))
    )
    (net (code "33") (name "/GPIO3_12") (class "Default")
      (node (ref "P20") (pin "9") (pinfunction "Pin_9_9") (pintype "passive"))
      (node (ref "U23") (pin "C6") (pinfunction "P7_4_C6") (pintype "passive"))
    )
    (net (code "34") (name "/GPIO3_13") (class "Default")
      (node (ref "P20") (pin "10") (pinfunction "Pin_10_10") (pintype "passive"))
      (node (ref "U23") (pin "A7") (pinfunction "P7_5_A7") (pintype "passive"))
    )
    (net (code "35") (name "/GPIO3_14") (class "Default")
      (node (ref "P20") (pin "11") (pinfunction "Pin_11_11") (pintype "passive"))
      (node (ref "U23") (pin "F5") (pinfunction "P7_6_F5") (pintype "passive"))
    )
    (net (code "36") (name "/GPIO3_15") (class "Default")
      (node (ref "P20") (pin "12") (pinfunction "Pin_12_12") (pintype "passive"))
      (node (ref "U23") (pin "D5") (pinfunction "P7_7_D5") (pintype "passive"))
    )
    (net (code "37") (name "/I2C1_SCL") (class "Default")
      (node (ref "P22") (pin "5") (pinfunction "Pin_5_5") (pintype "passive"))
      (node (ref "U23") (pin "L9") (pinfunction "P2_4_L9") (pintype "passive"))
    )
    (net (code "38") (name "/I2C1_SDA") (class "Default")
      (node (ref "P22") (pin "6") (pinfunction "Pin_6_6") (pintype "passive"))
      (node (ref "U23") (pin "G11") (pinfunction "P2_3_G11") (pintype "passive"))
    )
    (net (code "39") (name "/I2S0_RX_SDA") (class "Default")
      (node (ref "P28") (pin "19") (pinfunction "Pin_19_19") (pintype "passive"))
      (node (ref "U23") (pin "K11") (pinfunction "P6_2_K11") (pintype "passive"))
    )
    (net (code "40") (name "/I2S0_RX_WS") (class "Default")
      (node (ref "P22") (pin "15") (pinfunction "Pin_15_15") (pintype "passive"))
      (node (ref "U23") (pin "D10") (pinfunction "P3_1_D10") (pintype "passive"))
    )
    (net (code "41") (name "/I2S0_TX_MCLK") (class "Default")
      (node (ref "P22") (pin "17") (pinfunction "Pin_17_17") (pintype "passive"))
      (node (ref "U23") (pin "P10") (pinfunction "CLK2_P10") (pintype "passive"))
    )
    (net (code "42") (name "/I2S0_TX_SCK") (class "Default")
      (node (ref "P22") (pin "16") (pinfunction "Pin_16_16") (pintype "passive"))
      (node (ref "U23") (pin "D12") (pinfunction "P3_0_D12") (pintype "passive"))
    )
    (net (code "43") (name "/I2S0_TX_SDA") (class "Default")
      (node (ref "P22") (pin "13") (pinfunction "Pin_13_13") (pintype "passive"))
      (node (ref "U23") (pin "D9") (pinfunction "P3_2_D9") (pintype "passive"))
    )
    (net (code "44") (name "/ISP") (class "Default")
      (node (ref "R59") (pin "2") (pinfunction "2_2") (pintype "passive"))
      (node (ref "U23") (pin "G12") (pinfunction "P2_7_G12") (pintype "passive"))
    )
    (net (code "45") (name "/LPF_EN") (class "Default")
      (node (ref "U23") (pin "H12") (pinfunction "PA_1_H12") (pintype "passive"))
    )
    (net (code "46") (name "/MCU_CLK") (class "Default")
      (node (ref "U23") (pin "F4") (pinfunction "P4_7_F4") (pintype "passive"))
    )
    (net (code "47") (name "/MIXER.ENBL") (class "Default")
      (node (ref "U23") (pin "P1") (pinfunction "P9_0_P1") (pintype "passive"))
    )
    (net (code "48") (name "/MIXER.LD") (class "Default")
      (node (ref "U23") (pin "M7") (pinfunction "PD_11_M7") (pintype "passive"))
    )
    (net (code "49") (name "/MIXER.SCLK") (class "Default")
      (node (ref "U23") (pin "L7") (pinfunction "P9_5_L7") (pintype "passive"))
    )
    (net (code "50") (name "/MIXER.SDATA") (class "Default")
      (node (ref "U23") (pin "M6") (pinfunction "P9_2_M6") (pintype "passive"))
    )
    (net (code "51") (name "/MIXER.~{{EN}}") (class "Default")
      (node (ref "U23") (pin "N7") (pinfunction "P5_4_N7") (pintype "passive"))
    )
    (net (code "52") (name "/MIXER.~{{RESET}}") (class "Default")
      (node (ref "U23") (pin "N8") (pinfunction "P5_5_N8") (pintype "passive"))
    )
    (net (code "53") (name "/MODE") (class "Default")
      (node (ref "U23") (pin "J2") (pinfunction "P4_9_J2") (pintype "passive"))
    )
    (net (code "54") (name "/P1_1") (class "Default")
      (node (ref "R67") (pin "1") (pinfunction "1_1") (pintype "passive"))
      (node (ref "U23") (pin "N1") (pinfunction "P1_1_N1") (pintype "passive"))
    )
    (net (code "55") (name "/P1_2") (class "Default")
      (node (ref "R68") (pin "2") (pinfunction "2_2") (pintype "passive"))
      (node (ref "U23") (pin "N2") (pinfunction "P1_2_N2") (pintype "passive"))
    )
    (net (code "56") (name "/P1_7") (class "Default")
      (node (ref "P28") (pin "22") (pinfunction "Pin_22_22") (pintype "passive"))
      (node (ref "U23") (pin "N4") (pinfunction "P1_7_N4") (pintype "passive"))
    )
    (net (code "57") (name "/P1_CTRL0") (class "Default")
      (node (ref "U23") (pin "F14") (pinfunction "P2_10_F14") (pintype "passive"))
    )
    (net (code "58") (name "/P1_CTRL1") (class "Default")
      (node (ref "U23") (pin "F12") (pinfunction "P6_8_F12") (pintype "passive"))
    )
    (net (code "59") (name "/P1_CTRL2") (class "Default")
      (node (ref "U23") (pin "H13") (pinfunction "P6_9_H13") (pintype "passive"))
    )
    (net (code "60") (name "/P2") (class "Default")
      (node (ref "P22") (pin "1") (pinfunction "Pin_1_1") (pintype "passive"))
    )
    (net (code "61") (name "/P2_5") (class "Default")
      (node (ref "U23") (pin "J12") (pinfunction "P2_5_J12") (pintype "passive"))
    )
    (net (code "62") (name "/P2_8") (class "Default")
      (node (ref "P22") (pin "23") (pinfunction "Pin_23_23") (pintype "passive"))
      (node (ref "R30") (pin "1") (pinfunction "1_1") (pintype "passive"))
      (node (ref "U23") (pin "H14") (pinfunction "P2_8_H14") (pintype "passive"))
    )
    (net (code "63") (name "/P2_9") (class "Default")
      (node (ref "P22") (pin "21") (pinfunction "Pin_21_21") (pintype "passive"))
      (node (ref "R93") (pin "2") (pinfunction "2_2") (pintype "passive"))
      (node (ref "U23") (pin "G14") (pinfunction "P2_9_G14") (pintype "passive"))
    )
    (net (code "64") (name "/P2_13") (class "Default")
      (node (ref "P22") (pin "22") (pinfunction "Pin_22_22") (pintype "passive"))
      (node (ref "U23") (pin "E14") (pinfunction "P2_13_E14") (pintype "passive"))
    )
    (net (code "65") (name "/P2_CTRL0") (class "Default")
      (node (ref "U23") (pin "K10") (pinfunction "PE_3_K10") (pintype "passive"))
    )
    (net (code "66") (name "/P2_CTRL1") (class "Default")
      (node (ref "U23") (pin "J11") (pinfunction "PE_4_J11") (pintype "passive"))
    )
    (net (code "67") (name "/P5_3") (class "Default")
      (node (ref "P28") (pin "21") (pinfunction "Pin_21_21") (pintype "passive"))
      (node (ref "U23") (pin "P6") (pinfunction "P5_3_P6") (pintype "passive"))
    )
    (net (code "68") (name "/P5_6") (class "Default")
      (node (ref "P28") (pin "13") (pinfunction "Pin_13_13") (pintype "passive"))
      (node (ref "U23") (pin "M11") (pinfunction "P5_6_M11") (pintype "passive"))
    )
    (net (code "69") (name "/P5_7") (class "Default")
      (node (ref "P28") (pin "14") (pinfunction "Pin_14_14") (pintype "passive"))
      (node (ref "U23") (pin "N11") (pinfunction "P5_7_N11") (pintype "passive"))
    )
    (net (code "70") (name "/P9_1") (class "Default")
      (node (ref "P28") (pin "20") (pinfunction "Pin_20_20") (pintype "passive"))
      (node (ref "U23") (pin "P4") (pinfunction "P9_1_P4") (pintype "passive"))
    )
    (net (code "71") (name "/P22_CLKIN") (class "Default")
      (node (ref "P22") (pin "2") (pinfunction "Pin_2_2") (pintype "passive"))
    )
    (net (code "72") (name "/PA_3") (class "Default")
      (node (ref "P22") (pin "12") (pinfunction "Pin_12_12") (pintype "passive"))
      (node (ref "U23") (pin "E10") (pinfunction "PA_3_E10") (pintype "passive"))
    )
    (net (code "73") (name "/PA_4") (class "Default")
      (node (ref "P22") (pin "9") (pinfunction "Pin_9_9") (pintype "passive"))
      (node (ref "U23") (pin "E12") (pinfunction "PA_4_E12") (pintype "passive"))
    )
    (net (code "74") (name "/PB_0") (class "Default")
      (node (ref "P22") (pin "14") (pinfunction "Pin_14_14") (pintype "passive"))
      (node (ref "U23") (pin "D14") (pinfunction "PB_0_D14") (pintype "passive"))
    )
    (net (code "75") (name "/PB_1") (class "Default")
      (node (ref "P22") (pin "7") (pinfunction "Pin_7_7") (pintype "passive"))
      (node (ref "U23") (pin "A13") (pinfunction "PB_1_A13") (pintype "passive"))
    )
    (net (code "76") (name "/PB_3") (class "Default")
      (node (ref "P22") (pin "8") (pinfunction "Pin_8_8") (pintype "passive"))
      (node (ref "U23") (pin "A12") (pinfunction "PB_3_A12") (pintype "passive"))
    )
    (net (code "77") (name "/PB_5") (class "Default")
      (node (ref "P20") (pin "2") (pinfunction "Pin_2_2") (pintype "passive"))
      (node (ref "U23") (pin "A11") (pinfunction "PB_5_A11") (pintype "passive"))
    )
    (net (code "78") (name "/PE_0") (class "Default")
      (node (ref "P28") (pin "18") (pinfunction "Pin_18_18") (pintype "passive"))
      (node (ref "U23") (pin "N12") (pinfunction "PE_0_N12") (pintype "passive"))
    )
    (net (code "79") (name "/RF_AMP_EN") (class "Default")
      (node (ref "U23") (pin "J13") (pinfunction "PA_2_J13") (pintype "passive"))
    )
    (net (code "80") (name "/RREF") (class "Default")
      (node (ref "R69") (pin "2") (pinfunction "2_2") (pintype "passive"))
      (node (ref "U23") (pin "G1") (pinfunction "USB0_RREF_G1") (pintype "passive"))
    )
    (net (code "81") (name "/RTCX1") (class "Default")
      (node (ref "C118") (pin "1") (pinfunction "1_1") (pintype "passive"))
      (node (ref "U23") (pin "A8") (pinfunction "RTCX1_A8") (pintype "passive"))
      (node (ref "X3") (pin "2") (pinfunction "2_2") (pintype "passive"))
    )
    (net (code "82") (name "/RTCX2") (class "Default")
      (node (ref "C164") (pin "1") (pinfunction "1_1") (pintype "passive"))
      (node (ref "U23") (pin "B7") (pinfunction "RTCX2_B7") (pintype "passive"))
      (node (ref "X3") (pin "1") (pinfunction "1_1") (pintype "passive"))
    )
    (net (code "83") (name "/SCL") (class "Default")
      (node (ref "P22") (pin "26") (pinfunction "Pin_26_26") (pintype "passive"))
      (node (ref "U23") (pin "K13") (pinfunction "I2C0_SCL_K13") (pintype "passive"))
    )
    (net (code "84") (name "/SCT_CLK") (class "Default")
      (node (ref "U23") (pin "M14") (pinfunction "P6_4_M14") (pintype "passive"))
    )
    (net (code "85") (name "/SDA") (class "Default")
      (node (ref "P22") (pin "24") (pinfunction "Pin_24_24") (pintype "passive"))
      (node (ref "U23") (pin "K14") (pinfunction "I2C0_SDA_K14") (pintype "passive"))
    )
    (net (code "86") (name "/SD_CD") (class "Default")
      (node (ref "P28") (pin "3") (pinfunction "Pin_3_3") (pintype "passive"))
      (node (ref "U23") (pin "L8") (pinfunction "P1_13_L8") (pintype "passive"))
    )
    (net (code "87") (name "/SD_CLK") (class "Default")
      (node (ref "P28") (pin "11") (pinfunction "Pin_11_11") (pintype "passive"))
      (node (ref "U23") (pin "M4") (pinfunction "CLK0_M4") (pintype "passive"))
    )
    (net (code "88") (name "/SD_CMD") (class "Default")
      (node (ref "P28") (pin "9") (pinfunction "Pin_9_9") (pintype "passive"))
      (node (ref "U23") (pin "P3") (pinfunction "P1_6_P3") (pintype "passive"))
    )
    (net (code "89") (name "/SD_DAT0") (class "Default")
      (node (ref "P28") (pin "7") (pinfunction "Pin_7_7") (pintype "passive"))
      (node (ref "U23") (pin "N5") (pinfunction "P1_9_N5") (pintype "passive"))
    )
    (net (code "90") (name "/SD_DAT1") (class "Default")
      (node (ref "P28") (pin "6") (pinfunction "Pin_6_6") (pintype "passive"))
      (node (ref "U23") (pin "N6") (pinfunction "P1_10_N6") (pintype "passive"))
    )
    (net (code "91") (name "/SD_DAT2") (class "Default")
      (node (ref "P28") (pin "5") (pinfunction "Pin_5_5") (pintype "passive"))
      (node (ref "U23") (pin "P8") (pinfunction "P1_11_P8") (pintype "passive"))
    )
    (net (code "92") (name "/SD_DAT3") (class "Default")
      (node (ref "P28") (pin "4") (pinfunction "Pin_4_4") (pintype "passive"))
      (node (ref "U23") (pin "P7") (pinfunction "P1_12_P7") (pintype "passive"))
    )
    (net (code "93") (name "/SD_POW") (class "Default")
      (node (ref "P28") (pin "10") (pinfunction "Pin_10_10") (pintype "passive"))
      (node (ref "U23") (pin "N3") (pinfunction "P1_5_N3") (pintype "passive"))
    )
    (net (code "94") (name "/SD_VOLT0") (class "Default")
      (node (ref "P28") (pin "8") (pinfunction "Pin_8_8") (pintype "passive"))
      (node (ref "U23") (pin "M5") (pinfunction "P1_8_M5") (pintype "passive"))
    )
    (net (code "95") (name "/SGPIO0") (class "Default")
      (node (ref "U23") (pin "K3") (pinfunction "P0_0_K3") (pintype "passive"))
    )
    (net (code "96") (name "/SGPIO1") (class "Default")
      (node (ref "U23") (pin "K2") (pinfunction "P0_1_K2") (pintype "passive"))
    )
    (net (code "97") (name "/SGPIO2") (class "Default")
      (node (ref "U23") (pin "P11") (pinfunction "P1_15_P11") (pintype "passive"))
    )
    (net (code "98") (name "/SGPIO3") (class "Default")
      (node (ref "U23") (pin "L5") (pinfunction "P1_16_L5") (pintype "passive"))
    )
    (net (code "99") (name "/SGPIO4") (class "Default")
      (node (ref "U23") (pin "M8") (pinfunction "P9_4_M8") (pintype "passive"))
    )
    (net (code "100") (name "/SGPIO5") (class "Default")
      (node (ref "U23") (pin "K12") (pinfunction "P6_6_K12") (pintype "passive"))
    )
    (net (code "101") (name "/SGPIO6") (class "Default")
      (node (ref "U23") (pin "L13") (pinfunction "P2_2_L13") (pintype "passive"))
    )
    (net (code "102") (name "/SGPIO7") (class "Default")
      (node (ref "U23") (pin "L1") (pinfunction "P1_0_L1") (pintype "passive"))
    )
    (net (code "103") (name "/SGPIO8") (class "Default")
      (node (ref "U23") (pin "E4") (pinfunction "P8_0_E4") (pintype "passive"))
    )
    (net (code "104") (name "/SGPIO9") (class "Default")
      (node (ref "U23") (pin "P5") (pinfunction "P9_3_P5") (pintype "passive"))
    )
    (net (code "105") (name "/SGPIO10") (class "Default")
      (node (ref "U23") (pin "J4") (pinfunction "P8_2_J4") (pintype "passive"))
    )
    (net (code "106") (name "/SGPIO11") (class "Default")
      (node (ref "U23") (pin "L6") (pinfunction "P1_17_L6") (pintype "passive"))
    )
    (net (code "107") (name "/SGPIO12") (class "Default")
      (node (ref "U23") (pin "N10") (pinfunction "P1_18_N10") (pintype "passive"))
    )
    (net (code "108") (name "/SPIFI_CIPO") (class "Default")
      (node (ref "U20") (pin "2") (pinfunction "DO/IO_{1}_2") (pintype "passive"))
      (node (ref "U23") (pin "B12") (pinfunction "P3_6_B12") (pintype "passive"))
    )
    (net (code "109") (name "/SPIFI_COPI") (class "Default")
      (node (ref "U20") (pin "5") (pinfunction "DI/IO_{0}_5") (pintype "passive"))
      (node (ref "U23") (pin "C10") (pinfunction "P3_7_C10") (pintype "passive"))
    )
    (net (code "110") (name "/SPIFI_SCK") (class "Default")
      (node (ref "U20") (pin "6") (pinfunction "CLK_6") (pintype "passive"))
      (node (ref "U23") (pin "B13") (pinfunction "P3_3_B13") (pintype "passive"))
    )
    (net (code "111") (name "/SPIFI_SIO2") (class "Default")
      (node (ref "U20") (pin "3") (pinfunction "~{{WP}/IO_{2}}_3") (pintype "passive"))
      (node (ref "U23") (pin "C11") (pinfunction "P3_5_C11") (pintype "passive"))
    )
    (net (code "112") (name "/SPIFI_SIO3") (class "Default")
      (node (ref "U20") (pin "7") (pinfunction "~{{HOLD}/}{RESET}/IO_{3}_7") (pintype "passive"))
      (node (ref "U23") (pin "C14") (pinfunction "P3_4_C14") (pintype "passive"))
    )
    (net (code "113") (name "/SPIFI_~{{CS}}") (class "Default")
      (node (ref "TP64") (pin "1") (pinfunction "1_1") (pintype "passive"))
      (node (ref "U20") (pin "1") (pinfunction "~{{CS}}_1") (pintype "passive"))
      (node (ref "U23") (pin "C9") (pinfunction "P3_8_C9") (pintype "passive"))
    )
    (net (code "114") (name "/SSP1_CIPO") (class "Default")
      (node (ref "U23") (pin "M2") (pinfunction "P1_3_M2") (pintype "passive"))
    )
    (net (code "115") (name "/SSP1_COPI") (class "Default")
      (node (ref "R140") (pin "1") (pinfunction "1_1") (pintype "passive"))
    )
    (net (code "116") (name "/SSP1_SCK") (class "Default")
      (node (ref "R141") (pin "1") (pinfunction "1_1") (pintype "passive"))
    )
    (net (code "117") (name "/TCK") (class "Default")
      (node (ref "P26") (pin "4") (pinfunction "Pin_4_4") (pintype "passive"))
      (node (ref "R66") (pin "2") (pinfunction "2_2") (pintype "passive"))
      (node (ref "TP25") (pin "1") (pinfunction "1_1") (pintype "passive"))
      (node (ref "U23") (pin "G5") (pinfunction "TCK/SWDCLK_G5") (pintype "passive"))
    )
    (net (code "118") (name "/TDI") (class "Default")
      (node (ref "P26") (pin "8") (pinfunction "Pin_8_8") (pintype "passive"))
      (node (ref "TP28") (pin "1") (pinfunction "1_1") (pintype "passive"))
      (node (ref "U23") (pin "H4") (pinfunction "TDI_H4") (pintype "passive"))
    )
    (net (code "119") (name "/TDO") (class "Default")
      (node (ref "P26") (pin "6") (pinfunction "Pin_6_6") (pintype "passive"))
      (node (ref "R63") (pin "2") (pinfunction "2_2") (pintype "passive"))
      (node (ref "TP27") (pin "1") (pinfunction "1_1") (pintype "passive"))
      (node (ref "U23") (pin "J5") (pinfunction "TDO/SWO_J5") (pintype "passive"))
    )
    (net (code "120") (name "/TMS") (class "Default")
      (node (ref "P26") (pin "2") (pinfunction "Pin_2_2") (pintype "passive"))
      (node (ref "TP26") (pin "1") (pinfunction "1_1") (pintype "passive"))
      (node (ref "U23") (pin "K5") (pinfunction "TMS/SWDIO_K5") (pintype "passive"))
    )
    (net (code "121") (name "/TRIGGER.IN") (class "Default")
      (node (ref "P28") (pin "16") (pinfunction "Pin_16_16") (pintype "passive"))
      (node (ref "R127") (pin "2") (pinfunction "2_2") (pintype "passive"))
    )
    (net (code "122") (name "/TRIGGER.OUT") (class "Default")
      (node (ref "P28") (pin "15") (pinfunction "Pin_15_15") (pintype "passive"))
      (node (ref "R6") (pin "1") (pinfunction "1_1") (pintype "passive"))
    )
    (net (code "123") (name "/TX_EN") (class "Default")
      (node (ref "U23") (pin "L14") (pinfunction "P6_5_L14") (pintype "passive"))
    )
    (net (code "124") (name "/U0_RXD") (class "Default")
      (node (ref "P22") (pin "19") (pinfunction "Pin_19_19") (pintype "passive"))
      (node (ref "U23") (pin "M13") (pinfunction "P2_1_M13") (pintype "passive"))
    )
    (net (code "125") (name "/U0_TXD") (class "Default")
      (node (ref "P22") (pin "20") (pinfunction "Pin_20_20") (pintype "passive"))
      (node (ref "U23") (pin "N14") (pinfunction "P2_0_N14") (pintype "passive"))
    )
    (net (code "126") (name "/USB0_VBUS") (class "Default")
      (node (ref "R62") (pin "2") (pinfunction "2_2") (pintype "passive"))
      (node (ref "R65") (pin "1") (pinfunction "1_1") (pintype "passive"))
      (node (ref "U23") (pin "E1") (pinfunction "USB0_VBUS_E1") (pintype "passive"))
    )
    (net (code "127") (name "/USB_DATA.D+") (class "Default")
      (node (ref "U23") (pin "E2") (pinfunction "USB0_DP_E2") (pintype "passive"))
    )
    (net (code "128") (name "/USB_DATA.D-") (class "Default")
      (node (ref "U23") (pin "F2") (pinfunction "USB0_DM_F2") (pintype "passive"))
    )
    (net (code "129") (name "/VBAT") (class "Default")
      (node (ref "C136") (pin "1") (pinfunction "1_1") (pintype "passive"))
      (node (ref "P20") (pin "1") (pinfunction "Pin_1_1") (pintype "passive"))
      (node (ref "U23") (pin "B9") (pinfunction "VBAT_B9") (pintype "passive"))
    )
    (net (code "130") (name "/VBUS") (class "Default")
      (node (ref "P20") (pin "21") (pinfunction "Pin_21_21") (pintype "passive"))
    )
    (net (code "131") (name "/VBUSCTRL") (class "Default")
      (node (ref "P20") (pin "17") (pinfunction "Pin_17_17") (pintype "passive"))
      (node (ref "R37") (pin "1") (pinfunction "1_1") (pintype "passive"))
    )
    (net (code "132") (name "/VBUS_SAFE") (class "Default")
      (node (ref "R62") (pin "1") (pinfunction "1_1") (pintype "passive"))
    )
    (net (code "133") (name "/VIN") (class "Default")
      (node (ref "P20") (pin "22") (pinfunction "Pin_22_22") (pintype "passive"))
    )
    (net (code "134") (name "/WAKEUP") (class "Default")
      (node (ref "P20") (pin "4") (pinfunction "Pin_4_4") (pintype "passive"))
      (node (ref "R48") (pin "2") (pinfunction "2_2") (pintype "passive"))
      (node (ref "U23") (pin "A9") (pinfunction "WAKEUP0_A9") (pintype "passive"))
    )
    (net (code "135") (name "/XCVR.LD") (class "Default")
      (node (ref "U23") (pin "M9") (pinfunction "P9_6_M9") (pintype "passive"))
    )
    (net (code "136") (name "/XCVR.RSSI") (class "Default")
      (node (ref "U23") (pin "C4") (pinfunction "ADC0_1/ADC1_1_C4") (pintype "passive"))
    )
    (net (code "137") (name "/XCVR.RXHP") (class "Default")
      (node (ref "U23") (pin "P13") (pinfunction "PD_15_P13") (pintype "passive"))
    )
    (net (code "138") (name "/XCVR.RXTX") (class "Default")
      (node (ref "U23") (pin "L12") (pinfunction "PE_2_L12") (pintype "passive"))
    )
    (net (code "139") (name "/XCVR.~{{CS}}") (class "Default")
      (node (ref "U23") (pin "L11") (pinfunction "PD_14_L11") (pintype "passive"))
    )
    (net (code "140") (name "/XCVR.~{{SHDN}}") (class "Default")
      (node (ref "U23") (pin "M12") (pinfunction "PE_1_M12") (pintype "passive"))
    )
    (net (code "141") (name "/XTAL1") (class "Default")
      (node (ref "C157") (pin "1") (pinfunction "1_1") (pintype "passive"))
      (node (ref "U23") (pin "C1") (pinfunction "XTAL1_C1") (pintype "passive"))
      (node (ref "X2") (pin "1") (pinfunction "1_1") (pintype "passive"))
    )
    (net (code "142") (name "/XTAL2") (class "Default")
      (node (ref "C158") (pin "1") (pinfunction "1_1") (pintype "passive"))
      (node (ref "U23") (pin "D1") (pinfunction "XTAL2_D1") (pintype "passive"))
      (node (ref "X2") (pin "3") (pinfunction "3_3") (pintype "passive"))
    )
    (net (code "153") (name "/~{{3V3AUX_EN}}") (class "Default")
      (node (ref "U23") (pin "H11") (pinfunction "P6_7_H11") (pintype "passive"))
    )
    (net (code "154") (name "/~{{3V3AUX_OC}}") (class "Default")
      (node (ref "U23") (pin "F11") (pinfunction "P6_11_F11") (pintype "passive"))
    )
    (net (code "155") (name "/~{{BIAS_EN}}") (class "Default")
      (node (ref "U23") (pin "D13") (pinfunction "P2_12_D13") (pintype "passive"))
    )
    (net (code "156") (name "/~{{BIAS_OC}}") (class "Default")
      (node (ref "U23") (pin "E13") (pinfunction "P2_11_E13") (pintype "passive"))
    )
    (net (code "157") (name "/~{{LED1}}") (class "Default")
      (node (ref "D4") (pin "2") (pinfunction "K1_2") (pintype "passive"))
      (node (ref "D4") (pin "4") (pinfunction "K2_4") (pintype "passive"))
      (node (ref "U23") (pin "D3") (pinfunction "P4_1_D3") (pintype "passive"))
    )
    (net (code "158") (name "/~{{LED2}}") (class "Default")
      (node (ref "D5") (pin "1") (pinfunction "K_1") (pintype "passive"))
      (node (ref "U23") (pin "A2") (pinfunction "P4_2_A2") (pintype "passive"))
    )
    (net (code "159") (name "/~{{LED3}}") (class "Default")
      (node (ref "D6") (pin "4") (pinfunction "K2_4") (pintype "passive"))
      (node (ref "U23") (pin "F13") (pinfunction "P6_12_F13") (pintype "passive"))
    )
    (net (code "160") (name "/~{{LED4}}") (class "Default")
      (node (ref "D7") (pin "2") (pinfunction "K1_2") (pintype "passive"))
      (node (ref "D7") (pin "4") (pinfunction "K2_4") (pintype "passive"))
      (node (ref "U23") (pin "J3") (pinfunction "P8_6_J3") (pintype "passive"))
    )
    (net (code "161") (name "/~{{MIX_EN}}") (class "Default")
      (node (ref "U23") (pin "N13") (pinfunction "P6_3_N13") (pintype "passive"))
    )
    (net (code "162") (name "/~{{RESET}}") (class "Default")
      (node (ref "P22") (pin "3") (pinfunction "Pin_3_3") (pintype "passive"))
      (node (ref "P26") (pin "10") (pinfunction "Pin_10_10") (pintype "passive"))
      (node (ref "R19") (pin "2") (pinfunction "2_2") (pintype "passive"))
      (node (ref "U23") (pin "C7") (pinfunction "~{{RESET}}_C7") (pintype "passive"))
    )
    (net (code "163") (name "/~{{TRST}}") (class "Default")
      (node (ref "TP5") (pin "1") (pinfunction "1_1") (pintype "passive"))
      (node (ref "U23") (pin "L4") (pinfunction "~{{TRST}}_L4") (pintype "passive"))
    )
    (net (code "164") (name "/~{{VBUS_IN_EN}}") (class "Default")
      (node (ref "U23") (pin "H2") (pinfunction "P8_4_H2") (pintype "passive"))
    )
    (net (code "165") (name "/~{{VIN_IN_EN}}") (class "Default")
      (node (ref "U23") (pin "H1") (pinfunction "P8_5_H1") (pintype "passive"))
    )
    (net (code "166") (name "3V3AUX") (class "Default")
      (node (ref "P20") (pin "3") (pinfunction "Pin_3_3") (pintype "passive"))
      (node (ref "P22") (pin "11") (pinfunction "Pin_11_11") (pintype "passive"))
      (node (ref "P28") (pin "1") (pinfunction "Pin_1_1") (pintype "passive"))
    )
    (net (code "167") (name "3V3FPGA") (class "Default")
      (node (ref "C140") (pin "1") (pinfunction "1_1") (pintype "passive"))
      (node (ref "R76") (pin "1") (pinfunction "1_1") (pintype "passive"))
    )
    (net (code "168") (name "3V3LED") (class "Default")
      (node (ref "C110") (pin "1") (pinfunction "1_1") (pintype "passive"))
      (node (ref "C124") (pin "1") (pinfunction "1_1") (pintype "passive"))
      (node (ref "C80") (pin "1") (pinfunction "1_1") (pintype "passive"))
      (node (ref "C81") (pin "1") (pinfunction "1_1") (pintype "passive"))
      (node (ref "R125") (pin "1") (pinfunction "1_1") (pintype "passive"))
      (node (ref "R49") (pin "1") (pinfunction "1_1") (pintype "passive"))
      (node (ref "R50") (pin "1") (pinfunction "1_1") (pintype "passive"))
      (node (ref "R72") (pin "1") (pinfunction "1_1") (pintype "passive"))
      (node (ref "R73") (pin "1") (pinfunction "1_1") (pintype "passive"))
      (node (ref "R74") (pin "1") (pinfunction "1_1") (pintype "passive"))
      (node (ref "R75") (pin "1") (pinfunction "1_1") (pintype "passive"))
      (node (ref "SW1") (pin "2") (pinfunction "2_2") (pintype "passive"))
    )
    (net (code "169") (name "GND") (class "Default")
      (node (ref "C110") (pin "2") (pinfunction "2_2") (pintype "passive"))
      (node (ref "C118") (pin "2") (pinfunction "2_2") (pintype "passive"))
      (node (ref "C124") (pin "2") (pinfunction "2_2") (pintype "passive"))
      (node (ref "C128") (pin "2") (pinfunction "2_2") (pintype "passive"))
      (node (ref "C129") (pin "2") (pinfunction "2_2") (pintype "passive"))
      (node (ref "C130") (pin "2") (pinfunction "2_2") (pintype "passive"))
      (node (ref "C131") (pin "2") (pinfunction "2_2") (pintype "passive"))
      (node (ref "C132") (pin "2") (pinfunction "2_2") (pintype "passive"))
      (node (ref "C133") (pin "2") (pinfunction "2_2") (pintype "passive"))
      (node (ref "C134") (pin "2") (pinfunction "2_2") (pintype "passive"))
      (node (ref "C135") (pin "2") (pinfunction "2_2") (pintype "passive"))
      (node (ref "C136") (pin "2") (pinfunction "2_2") (pintype "passive"))
      (node (ref "C137") (pin "2") (pinfunction "2_2") (pintype "passive"))
      (node (ref "C138") (pin "2") (pinfunction "2_2") (pintype "passive"))
      (node (ref "C140") (pin "2") (pinfunction "2_2") (pintype "passive"))
      (node (ref "C144") (pin "2") (pinfunction "2_2") (pintype "passive"))
      (node (ref "C157") (pin "2") (pinfunction "2_2") (pintype "passive"))
      (node (ref "C158") (pin "2") (pinfunction "2_2") (pintype "passive"))
      (node (ref "C162") (pin "2") (pinfunction "2_2") (pintype "passive"))
      (node (ref "C164") (pin "2") (pinfunction "2_2") (pintype "passive"))
      (node (ref "C80") (pin "2") (pinfunction "2_2") (pintype "passive"))
      (node (ref "C81") (pin "2") (pinfunction "2_2") (pintype "passive"))
      (node (ref "D2") (pin "1") (pinfunction "K_1") (pintype "passive"))
      (node (ref "D8") (pin "2") (pinfunction "K1_2") (pintype "passive"))
      (node (ref "P20") (pin "13") (pinfunction "Pin_13_13") (pintype "passive"))
      (node (ref "P20") (pin "15") (pinfunction "Pin_15_15") (pintype "passive"))
      (node (ref "P20") (pin "19") (pinfunction "Pin_19_19") (pintype "passive"))
      (node (ref "P22") (pin "10") (pinfunction "Pin_10_10") (pintype "passive"))
      (node (ref "P22") (pin "18") (pinfunction "Pin_18_18") (pintype "passive"))
      (node (ref "P22") (pin "4") (pinfunction "Pin_4_4") (pintype "passive"))
      (node (ref "P26") (pin "3") (pinfunction "Pin_3_3") (pintype "passive"))
      (node (ref "P26") (pin "5") (pinfunction "Pin_5_5") (pintype "passive"))
      (node (ref "P26") (pin "9") (pinfunction "Pin_9_9") (pintype "passive"))
      (node (ref "P28") (pin "12") (pinfunction "Pin_12_12") (pintype "passive"))
      (node (ref "P28") (pin "2") (pinfunction "Pin_2_2") (pintype "passive"))
      (node (ref "R107") (pin "1") (pinfunction "1_1") (pintype "passive"))
      (node (ref "R39") (pin "2") (pinfunction "2_2") (pintype "passive"))
      (node (ref "R65") (pin "2") (pinfunction "2_2") (pintype "passive"))
      (node (ref "R68") (pin "1") (pinfunction "1_1") (pintype "passive"))
      (node (ref "R69") (pin "1") (pinfunction "1_1") (pintype "passive"))
      (node (ref "R7") (pin "2") (pinfunction "2_2") (pintype "passive"))
      (node (ref "R82") (pin "2") (pinfunction "2_2") (pintype "passive"))
      (node (ref "R93") (pin "1") (pinfunction "1_1") (pintype "passive"))
      (node (ref "SW1") (pin "SH") (pinfunction "B_SH") (pintype "passive"))
      (node (ref "SW2") (pin "2") (pinfunction "2_2") (pintype "passive"))
      (node (ref "SW2") (pin "SH") (pinfunction "B_SH") (pintype "passive"))
      (node (ref "U20") (pin "4") (pinfunction "GND_4") (pintype "passive"))
      (node (ref "U23") (pin "A3") (pinfunction "VSSA_A3") (pintype "passive"))
      (node (ref "U23") (pin "D7") (pinfunction "VSS_D7") (pintype "passive"))
      (node (ref "U23") (pin "E6") (pinfunction "VSS_E6") (pintype "passive"))
      (node (ref "U23") (pin "E7") (pinfunction "VSS_E7") (pintype "passive"))
      (node (ref "U23") (pin "E9") (pinfunction "VSS_E9") (pintype "passive"))
      (node (ref "U23") (pin "F1") (pinfunction "USB0_VSSA_REF_F1") (pintype "passive"))
      (node (ref "U23") (pin "F10") (pinfunction "VSS_F10") (pintype "passive"))
      (node (ref "U23") (pin "G3") (pinfunction "USB0_VSSA_TERM_G3") (pintype "passive"))
      (node (ref "U23") (pin "K6") (pinfunction "VSS_K6") (pintype "passive"))
      (node (ref "U23") (pin "K9") (pinfunction "VSS_K9") (pintype "passive"))
      (node (ref "X2") (pin "2") (pinfunction "2_2") (pintype "passive"))
      (node (ref "X2") (pin "4") (pinfunction "4_4") (pintype "passive"))
    )
    (net (code "170") (name "Net-(D2-A)") (class "Default")
      (node (ref "D2") (pin "2") (pinfunction "A_2") (pintype "passive"))
      (node (ref "R18") (pin "2") (pinfunction "2_2") (pintype "passive"))
      (node (ref "TP10") (pin "1") (pinfunction "1_1") (pintype "passive"))
    )
    (net (code "171") (name "Net-(D4-A1)") (class "Default")
      (node (ref "D4") (pin "1") (pinfunction "A1_1") (pintype "passive"))
      (node (ref "R72") (pin "2") (pinfunction "2_2") (pintype "passive"))
      (node (ref "TP12") (pin "1") (pinfunction "1_1") (pintype "passive"))
    )
    (net (code "172") (name "Net-(D4-A2)") (class "Default")
      (node (ref "D4") (pin "3") (pinfunction "A2_3") (pintype "passive"))
      (node (ref "R125") (pin "2") (pinfunction "2_2") (pintype "passive"))
      (node (ref "TP11") (pin "1") (pinfunction "1_1") (pintype "passive"))
    )
    (net (code "173") (name "Net-(D5-A)") (class "Default")
      (node (ref "D5") (pin "2") (pinfunction "A_2") (pintype "passive"))
      (node (ref "R73") (pin "2") (pinfunction "2_2") (pintype "passive"))
      (node (ref "TP13") (pin "1") (pinfunction "1_1") (pintype "passive"))
    )
    (net (code "174") (name "Net-(D6-A2)") (class "Default")
      (node (ref "D6") (pin "3") (pinfunction "A2_3") (pintype "passive"))
      (node (ref "R74") (pin "2") (pinfunction "2_2") (pintype "passive"))
      (node (ref "TP14") (pin "1") (pinfunction "1_1") (pintype "passive"))
    )
    (net (code "175") (name "Net-(D7-A1)") (class "Default")
      (node (ref "D7") (pin "1") (pinfunction "A1_1") (pintype "passive"))
      (node (ref "R75") (pin "2") (pinfunction "2_2") (pintype "passive"))
      (node (ref "TP8") (pin "1") (pinfunction "1_1") (pintype "passive"))
    )
    (net (code "176") (name "Net-(D7-A2)") (class "Default")
      (node (ref "D7") (pin "3") (pinfunction "A2_3") (pintype "passive"))
      (node (ref "R50") (pin "2") (pinfunction "2_2") (pintype "passive"))
      (node (ref "TP7") (pin "1") (pinfunction "1_1") (pintype "passive"))
    )
    (net (code "177") (name "Net-(D8-A1)") (class "Default")
      (node (ref "D8") (pin "1") (pinfunction "A1_1") (pintype "passive"))
      (node (ref "R76") (pin "2") (pinfunction "2_2") (pintype "passive"))
      (node (ref "TP9") (pin "1") (pinfunction "1_1") (pintype "passive"))
    )
    (net (code "178") (name "Net-(R19-Pad1)") (class "Default")
      (node (ref "R19") (pin "1") (pinfunction "1_1") (pintype "passive"))
      (node (ref "R49") (pin "2") (pinfunction "2_2") (pintype "passive"))
      (node (ref "SW2") (pin "1") (pinfunction "1_1") (pintype "passive"))
      (node (ref "TP30") (pin "1") (pinfunction "1_1") (pintype "passive"))
    )
    (net (code "179") (name "Net-(R30-Pad2)") (class "Default")
      (node (ref "R30") (pin "2") (pinfunction "2_2") (pintype "passive"))
      (node (ref "R7") (pin "1") (pinfunction "1_1") (pintype "passive"))
      (node (ref "SW1") (pin "1") (pinfunction "1_1") (pintype "passive"))
      (node (ref "TP31") (pin "1") (pinfunction "1_1") (pintype "passive"))
    )
    (net (code "180") (name "Net-(U23-P1_4)") (class "Default")
      (node (ref "R140") (pin "2") (pinfunction "2_2") (pintype "passive"))
      (node (ref "U23") (pin "P2") (pinfunction "P1_4_P2") (pintype "passive"))
    )
    (net (code "181") (name "Net-(U23-P1_19)") (class "Default")
      (node (ref "R141") (pin "2") (pinfunction "2_2") (pintype "passive"))
      (node (ref "U23") (pin "N9") (pinfunction "P1_19_N9") (pintype "passive"))
    )
    (net (code "182") (name "Net-(U23-P2_6)") (class "Default")
      (node (ref "R6") (pin "2") (pinfunction "2_2") (pintype "passive"))
      (node (ref "U23") (pin "J14") (pinfunction "P2_6_J14") (pintype "passive"))
    )
    (net (code "183") (name "Net-(U23-P4_3)") (class "Default")
      (node (ref "R37") (pin "2") (pinfunction "2_2") (pintype "passive"))
      (node (ref "R82") (pin "1") (pinfunction "1_1") (pintype "passive"))
      (node (ref "U23") (pin "B2") (pinfunction "P4_3_B2") (pintype "passive"))
    )
    (net (code "184") (name "Net-(U23-P4_6)") (class "Default")
      (node (ref "R107") (pin "2") (pinfunction "2_2") (pintype "passive"))
      (node (ref "U23") (pin "B1") (pinfunction "P4_6_B1") (pintype "passive"))
    )
    (net (code "185") (name "Net-(U23-PD_12)") (class "Default")
      (node (ref "R127") (pin "1") (pinfunction "1_1") (pintype "passive"))
      (node (ref "U23") (pin "P9") (pinfunction "PD_12_P9") (pintype "passive"))
    )
    (net (code "186") (name "VAA") (class "Default")
      (node (ref "C162") (pin "1") (pinfunction "1_1") (pintype "passive"))
      (node (ref "R18") (pin "1") (pinfunction "1_1") (pintype "passive"))
    )
    (net (code "187") (name "VCC") (class "Default")
      (node (ref "C128") (pin "1") (pinfunction "1_1") (pintype "passive"))
      (node (ref "C129") (pin "1") (pinfunction "1_1") (pintype "passive"))
      (node (ref "C130") (pin "1") (pinfunction "1_1") (pintype "passive"))
      (node (ref "C131") (pin "1") (pinfunction "1_1") (pintype "passive"))
      (node (ref "C132") (pin "1") (pinfunction "1_1") (pintype "passive"))
      (node (ref "C133") (pin "1") (pinfunction "1_1") (pintype "passive"))
      (node (ref "C134") (pin "1") (pinfunction "1_1") (pintype "passive"))
      (node (ref "C135") (pin "1") (pinfunction "1_1") (pintype "passive"))
      (node (ref "C137") (pin "1") (pinfunction "1_1") (pintype "passive"))
      (node (ref "C138") (pin "1") (pinfunction "1_1") (pintype "passive"))
      (node (ref "C144") (pin "1") (pinfunction "1_1") (pintype "passive"))
      (node (ref "P26") (pin "1") (pinfunction "Pin_1_1") (pintype "passive"))
      (node (ref "R38") (pin "1") (pinfunction "1_1") (pintype "passive"))
      (node (ref "R48") (pin "1") (pinfunction "1_1") (pintype "passive"))
      (node (ref "R59") (pin "1") (pinfunction "1_1") (pintype "passive"))
      (node (ref "R63") (pin "1") (pinfunction "1_1") (pintype "passive"))
      (node (ref "R64") (pin "1") (pinfunction "1_1") (pintype "passive"))
      (node (ref "R66") (pin "1") (pinfunction "1_1") (pintype "passive"))
      (node (ref "R67") (pin "2") (pinfunction "2_2") (pintype "passive"))
      (node (ref "U20") (pin "8") (pinfunction "VCC_8") (pintype "passive"))
      (node (ref "U23") (pin "A6") (pinfunction "VDDA_A6") (pintype "passive"))
      (node (ref "U23") (pin "D8") (pinfunction "VDDREG_D8") (pintype "passive"))
      (node (ref "U23") (pin "E3") (pinfunction "USB0_VDDA3V3_DRIVER_E3") (pintype "passive"))
      (node (ref "U23") (pin "E8") (pinfunction "VDDREG_E8") (pintype "passive"))
      (node (ref "U23") (pin "F3") (pinfunction "USB0_VDDA3V3_F3") (pintype "passive"))
      (node (ref "U23") (pin "G10") (pinfunction "VDDIO_G10") (pintype "passive"))
      (node (ref "U23") (pin "H10") (pinfunction "VDDIO_H10") (pintype "passive"))
      (node (ref "U23") (pin "H5") (pinfunction "VDDIO_H5") (pintype "passive"))
      (node (ref "U23") (pin "K8") (pinfunction "VDDIO_K8") (pintype "passive"))
    )
    (net (code "188") (name "unconnected-(D6-A1-Pad1)") (class "Default")
      (node (ref "D6") (pin "1") (pinfunction "A1_1") (pintype "passive+no_connect"))
    )
    (net (code "189") (name "unconnected-(D6-K1-Pad2)") (class "Default")
      (node (ref "D6") (pin "2") (pinfunction "K1_2") (pintype "passive+no_connect"))
    )
    (net (code "190") (name "unconnected-(D8-A2-Pad3)") (class "Default")
      (node (ref "D8") (pin "3") (pinfunction "A2_3") (pintype "passive+no_connect"))
    )
    (net (code "191") (name "unconnected-(D8-K2-Pad4)") (class "Default")
      (node (ref "D8") (pin "4") (pinfunction "K2_4") (pintype "passive+no_connect"))
    )
    (net (code "192") (name "unconnected-(JP1-A-Pad1)") (class "Default")
      (node (ref "JP1") (pin "1") (pinfunction "A_1") (pintype "passive"))
    )
    (net (code "193") (name "unconnected-(JP1-B-Pad2)") (class "Default")
      (node (ref "JP1") (pin "2") (pinfunction "B_2") (pintype "passive"))
    )
    (net (code "194") (name "unconnected-(P26-Pin_7-Pad7)") (class "Default")
      (node (ref "P26") (pin "7") (pinfunction "Pin_7_7") (pintype "passive+no_connect"))
    )
    (net (code "195") (name "unconnected-(U23-NC-PadB8)") (class "Default")
      (node (ref "U23") (pin "B8") (pinfunction "NC_B8") (pintype "passive+no_connect"))
    )
    (net (code "196") (name "unconnected-(U23-P4_0-PadD4)") (class "Default")
      (node (ref "U23") (pin "D4") (pinfunction "P4_0_D4") (pintype "passive+no_connect"))
    )
    (net (code "197") (name "unconnected-(U23-P4_8-PadD2)") (class "Default")
      (node (ref "U23") (pin "D2") (pinfunction "P4_8_D2") (pintype "passive+no_connect"))
    )
    (net (code "198") (name "unconnected-(U23-P5_0-PadL2)") (class "Default")
      (node (ref "U23") (pin "L2") (pinfunction "P5_0_L2") (pintype "passive+no_connect"))
    )
    (net (code "199") (name "unconnected-(U23-P6_0-PadM10)") (class "Default")
      (node (ref "U23") (pin "M10") (pinfunction "P6_0_M10") (pintype "passive+no_connect"))
    )
    (net (code "200") (name "unconnected-(U23-P6_10-PadG13)") (class "Default")
      (node (ref "U23") (pin "G13") (pinfunction "P6_10_G13") (pintype "passive+no_connect"))
    )
    (net (code "201") (name "unconnected-(U23-P8_3-PadH3)") (class "Default")
      (node (ref "U23") (pin "H3") (pinfunction "P8_3_H3") (pintype "passive+no_connect"))
    )
    (net (code "202") (name "unconnected-(U23-P8_8-PadK1)") (class "Default")
      (node (ref "U23") (pin "K1") (pinfunction "P8_8_K1") (pintype "passive+no_connect"))
    )
    (net (code "203") (name "unconnected-(U23-PA_0-PadL10)") (class "Default")
      (node (ref "U23") (pin "L10") (pinfunction "PA_0_L10") (pintype "passive+no_connect"))
    )
    (net (code "204") (name "unconnected-(U23-PB_2-PadB11)") (class "Default")
      (node (ref "U23") (pin "B11") (pinfunction "PB_2_B11") (pintype "passive+no_connect"))
    )
    (net (code "205") (name "unconnected-(U23-PB_4-PadB10)") (class "Default")
      (node (ref "U23") (pin "B10") (pinfunction "PB_4_B10") (pintype "passive+no_connect"))
    )
    (net (code "206") (name "unconnected-(U23-RTC_ALARM-PadA10)") (class "Default")
      (node (ref "U23") (pin "A10") (pinfunction "RTC_ALARM_A10") (pintype "passive+no_connect"))
    )
    (net (code "207") (name "unconnected-(U23-USB0_ID-PadG2)") (class "Default")
      (node (ref "U23") (pin "G2") (pinfunction "USB0_ID_G2") (pintype "passive+no_connect"))
    )
    (net (code "208") (name "unconnected-(U23-USB1_DM-PadE11)") (class "Default")
      (node (ref "U23") (pin "E11") (pinfunction "USB1_DM_E11") (pintype "passive+no_connect"))
    )
    (net (code "209") (name "unconnected-(U23-USB1_DP-PadD11)") (class "Default")
      (node (ref "U23") (pin "D11") (pinfunction "USB1_DP_D11") (pintype "passive+no_connect"))
    )
    (net (code "210") (name "unconnected-(U23-WAKEUP1-PadC8)") (class "Default")
      (node (ref "U23") (pin "C8") (pinfunction "WAKEUP1_C8") (pintype "passive+no_connect"))
    )
    (net (code "211") (name "unconnected-(U23-WAKEUP2-PadE5)") (class "Default")
      (node (ref "U23") (pin "E5") (pinfunction "WAKEUP2_E5") (pintype "passive+no_connect"))
    )
  )
)
